# xen_teensy_motherboard_matrix_mki.net
KiCad netlist of a schematic drawn in EAGLE
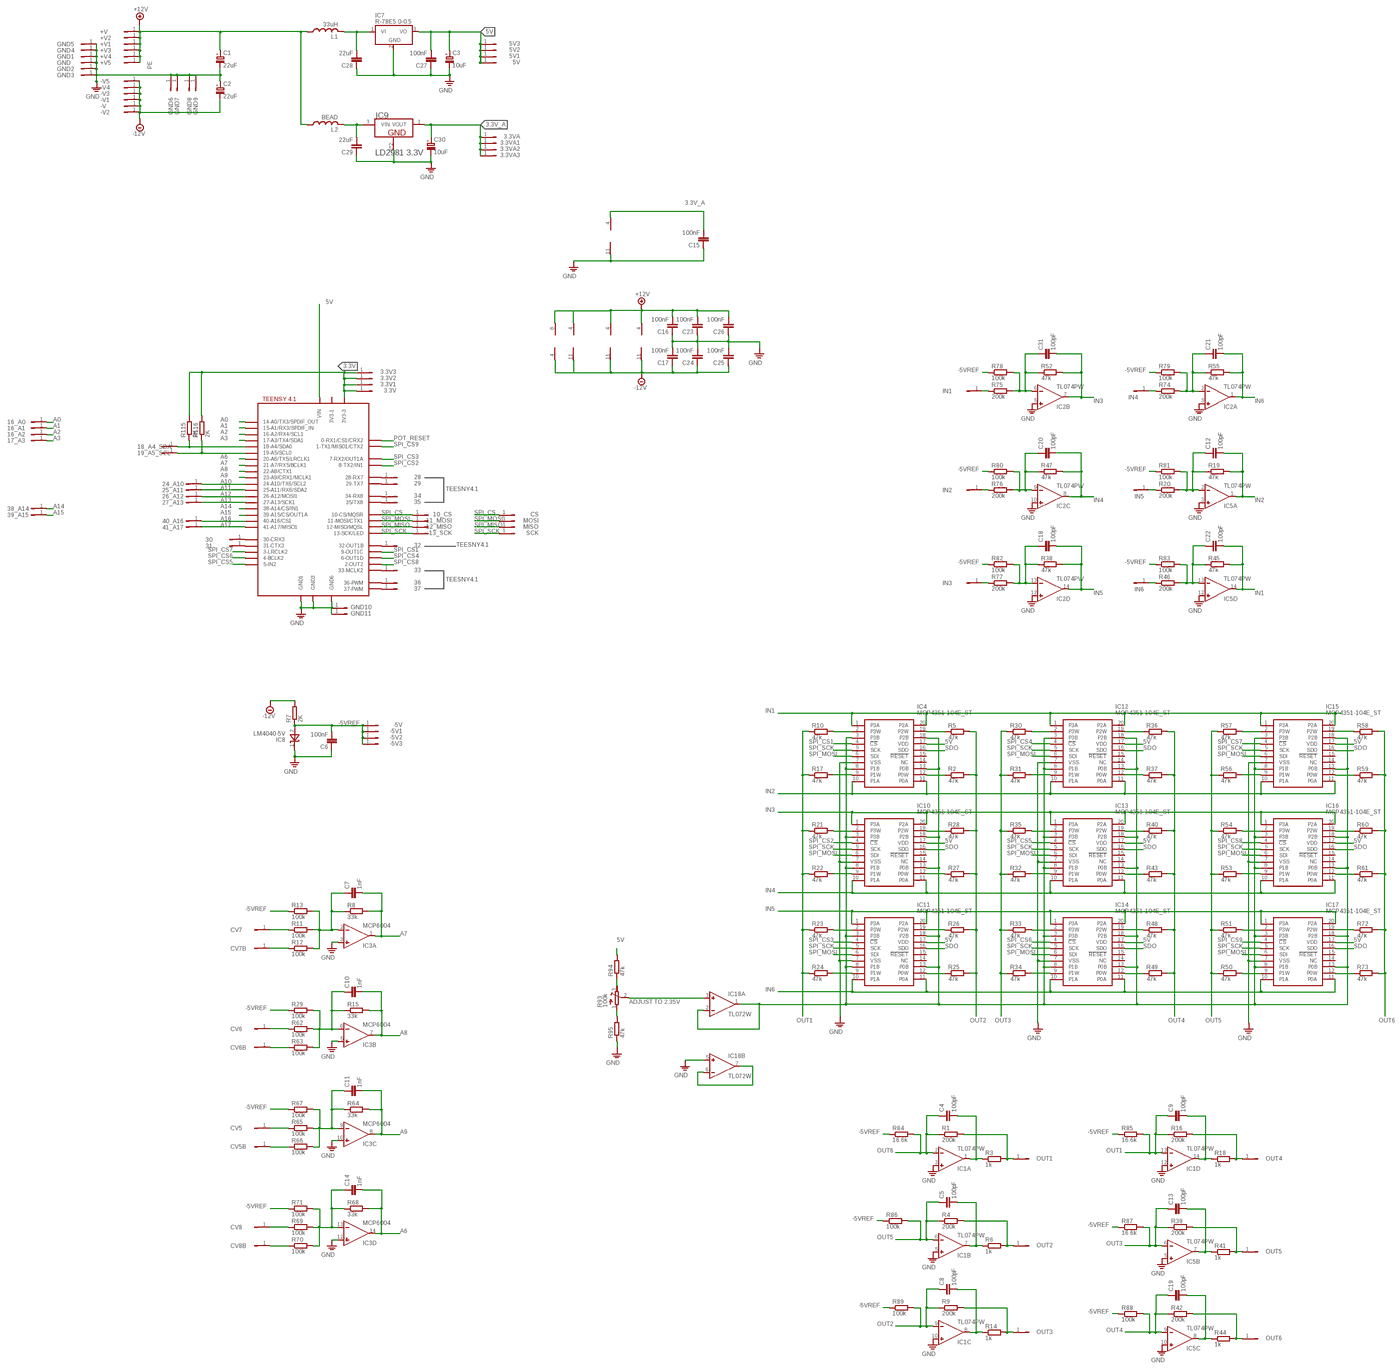
[diagram p0: schematic, sheet 1, overview]
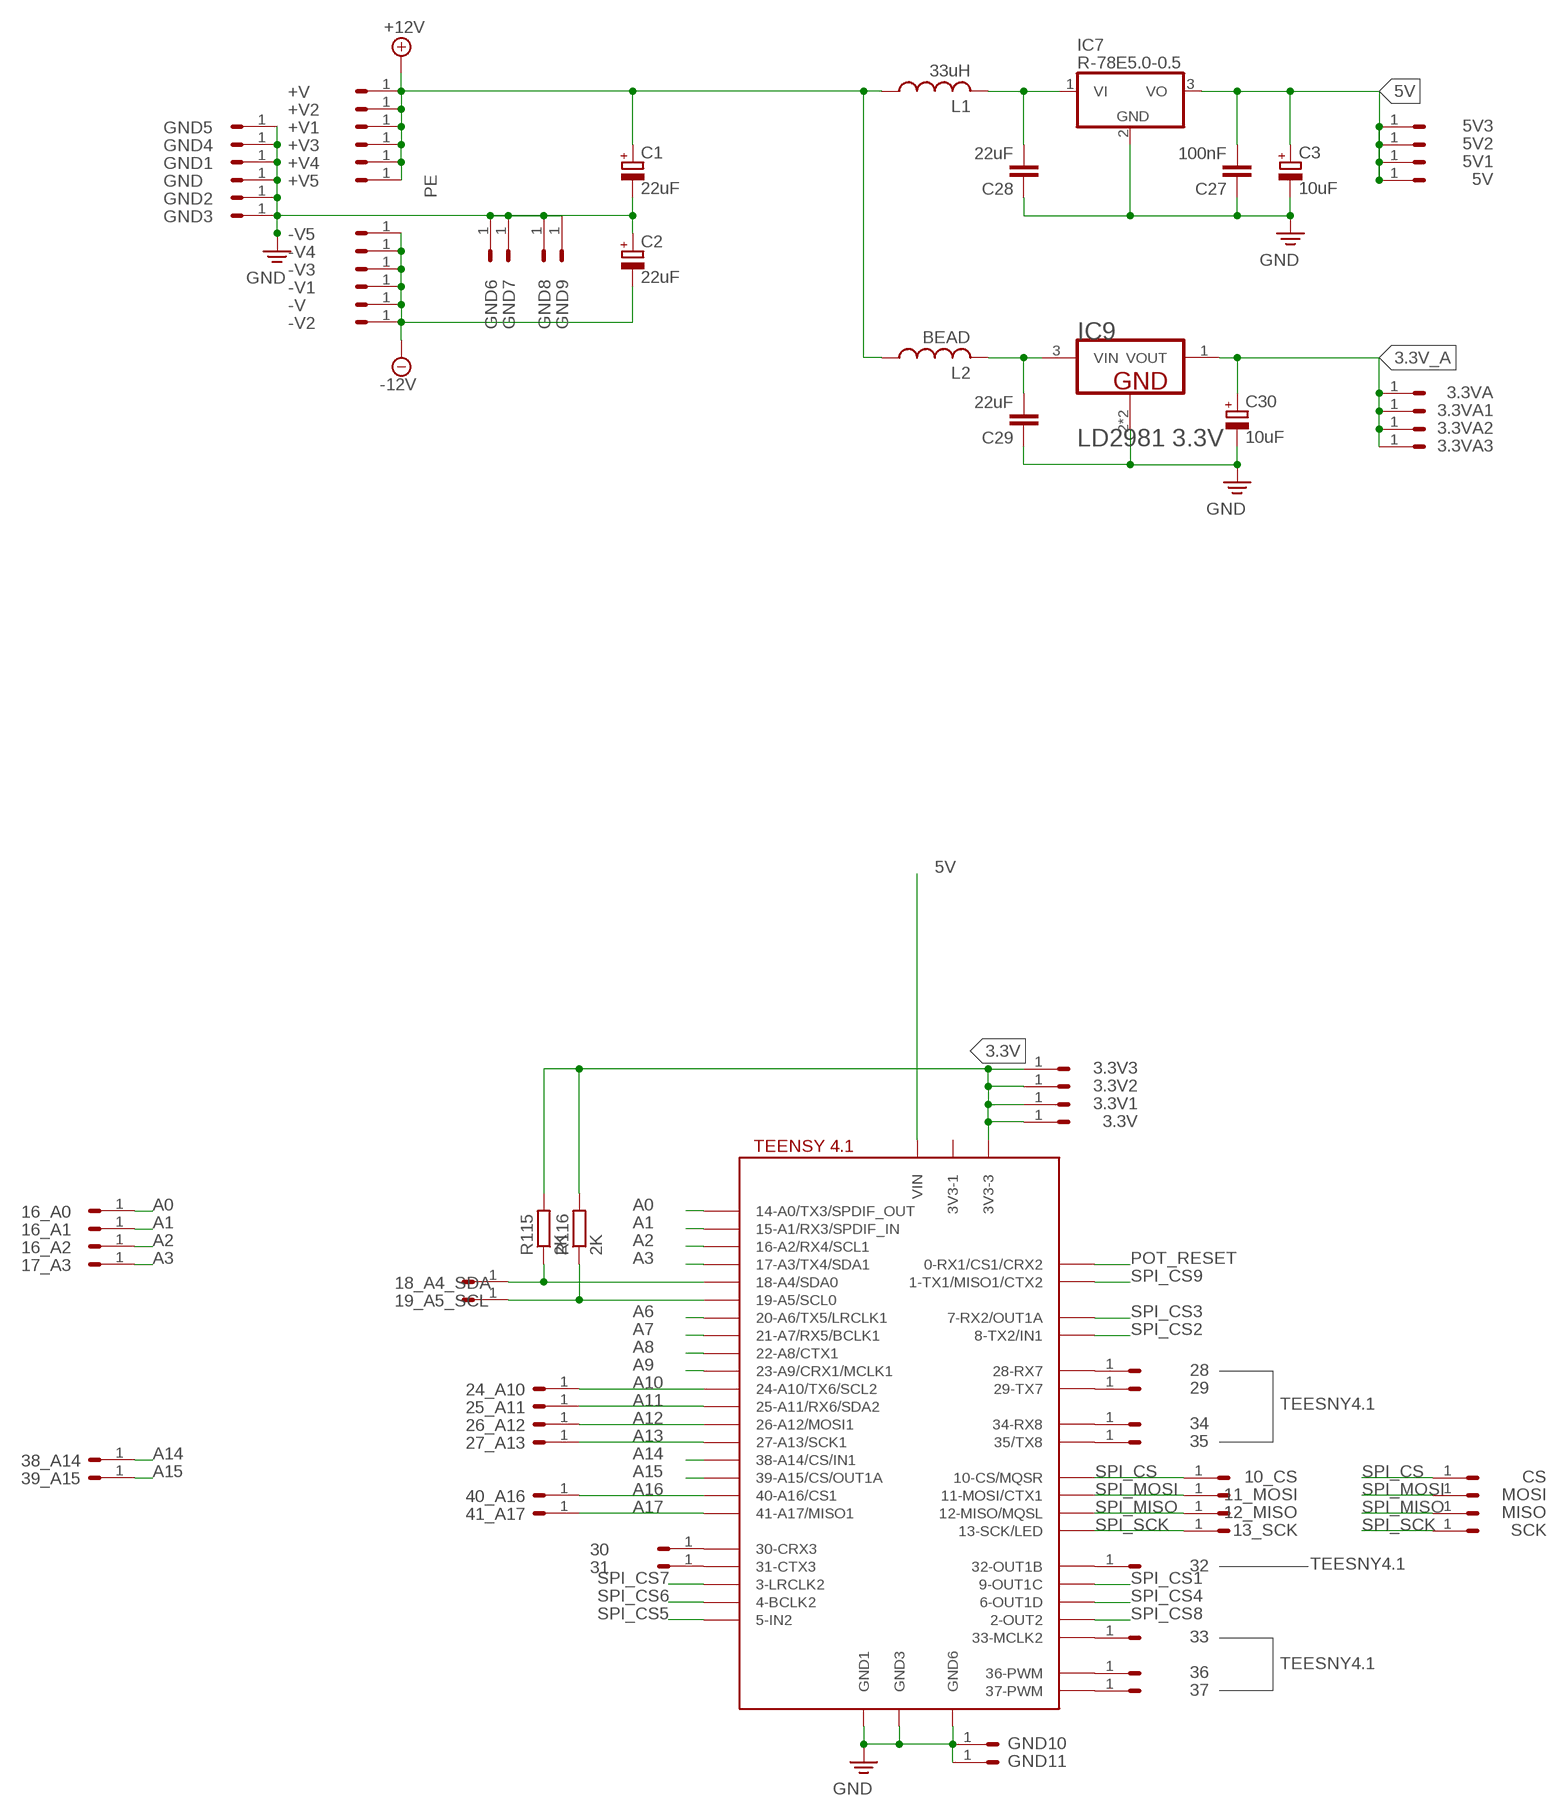
[diagram p1: schematic, sheet 1, part 1 of 4]
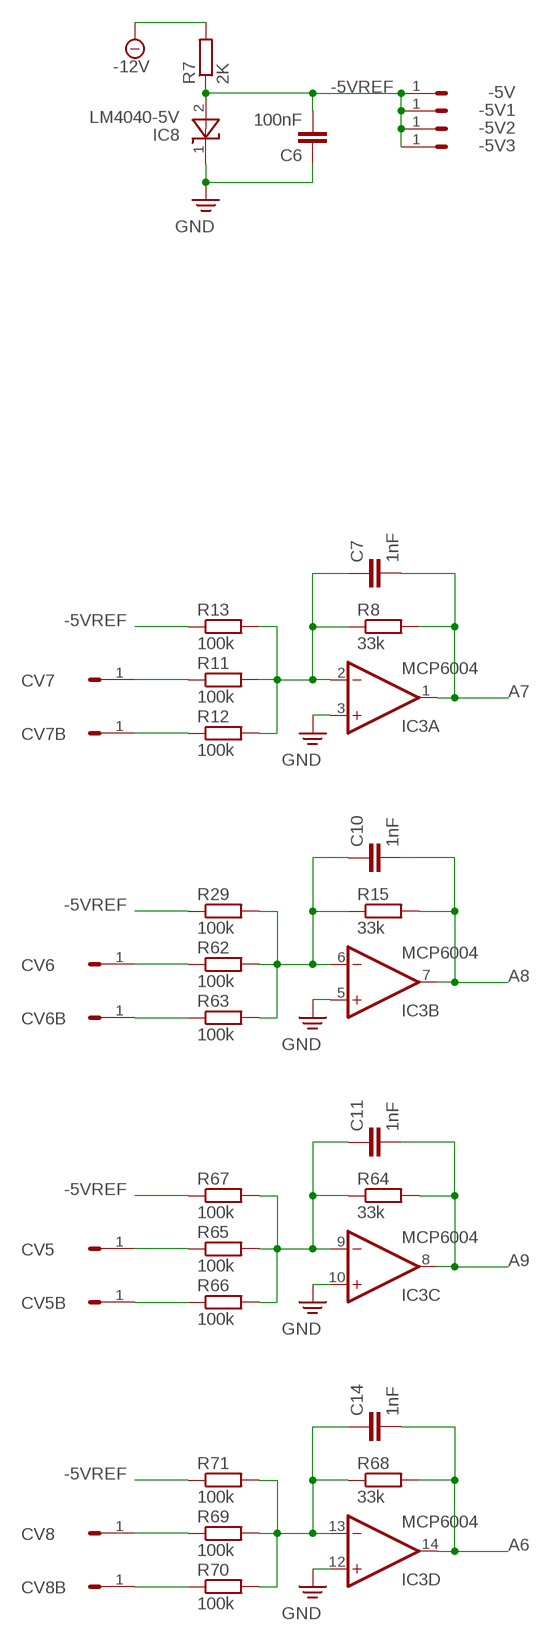
[diagram p2: schematic, sheet 1, part 2 of 4]
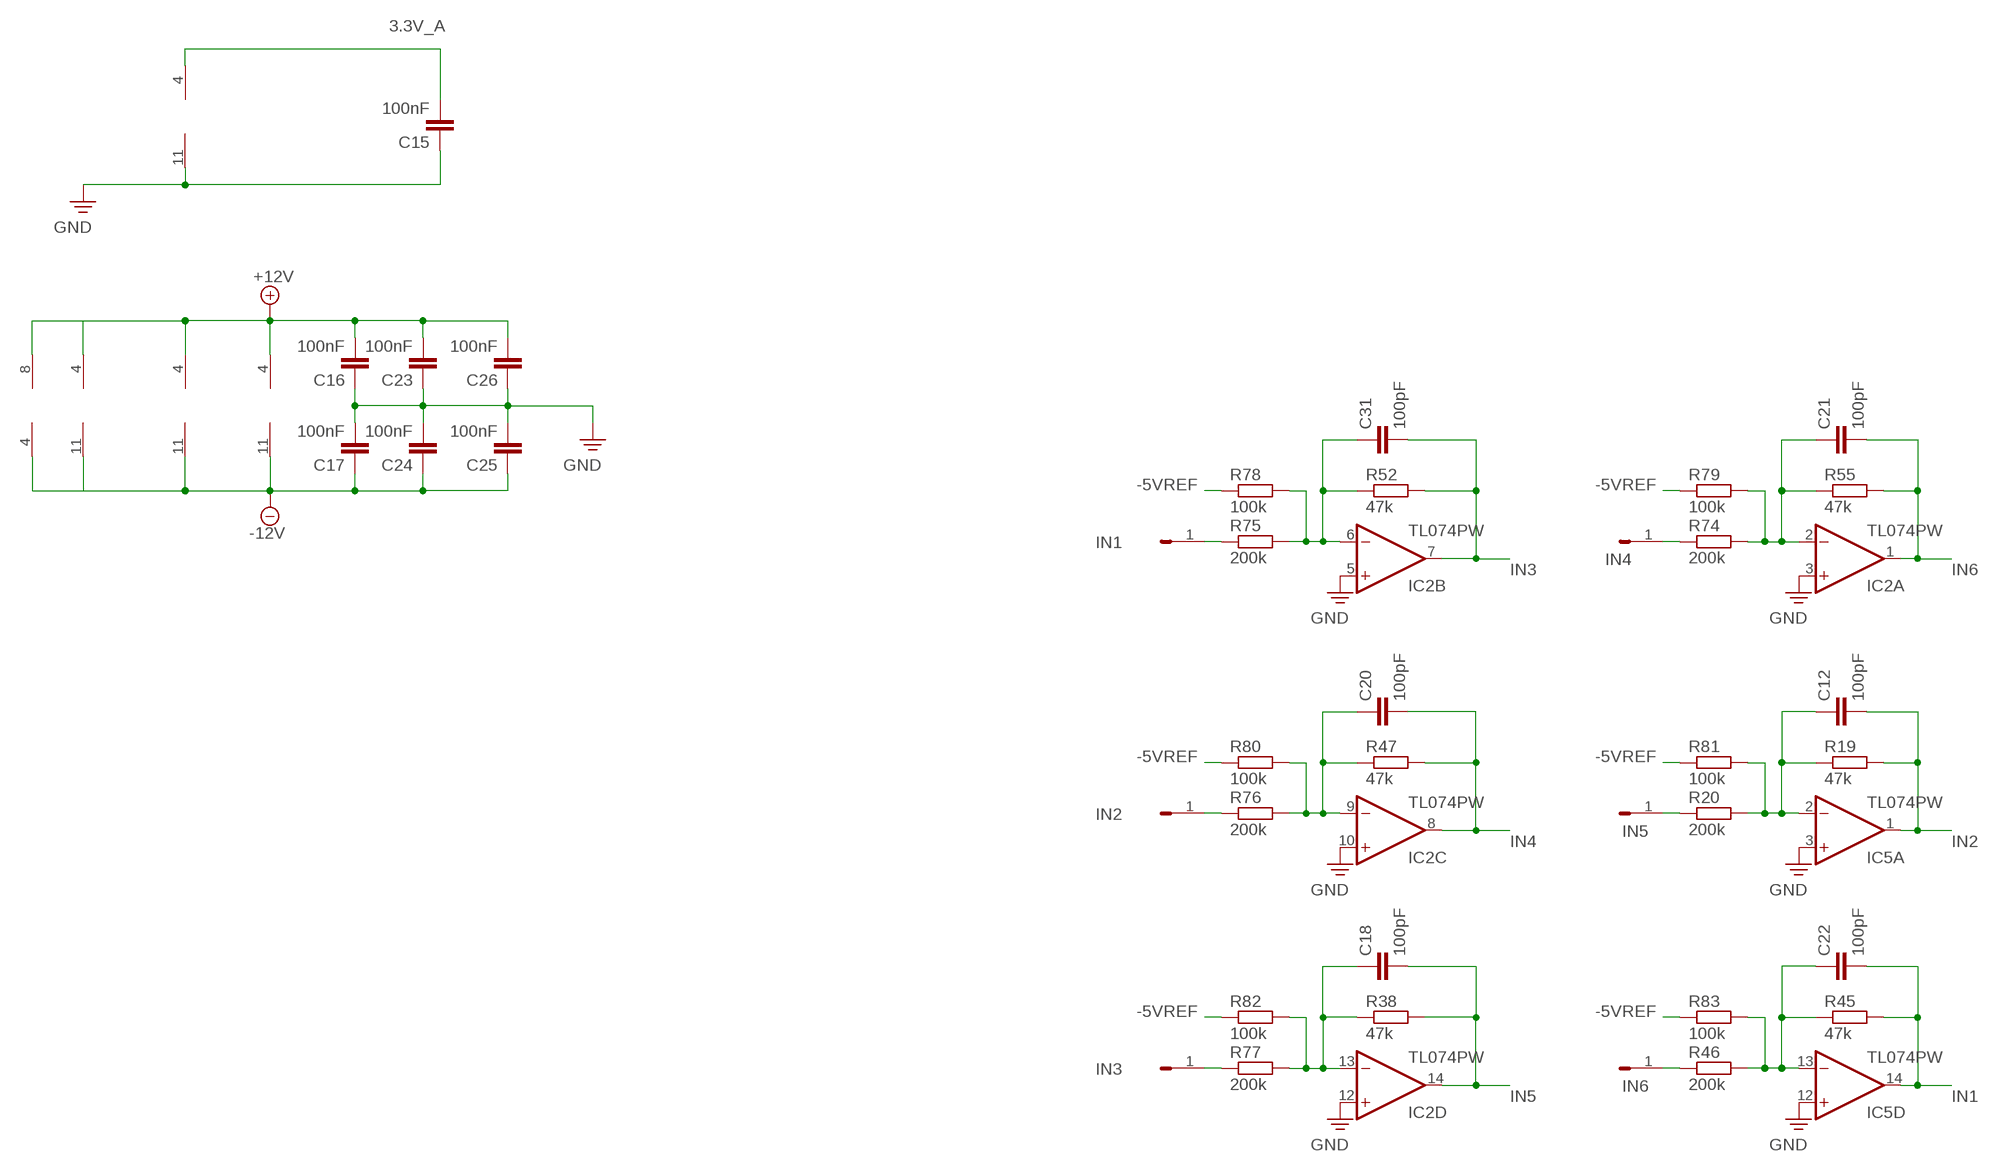
[diagram p3: schematic, sheet 1, part 3 of 4]
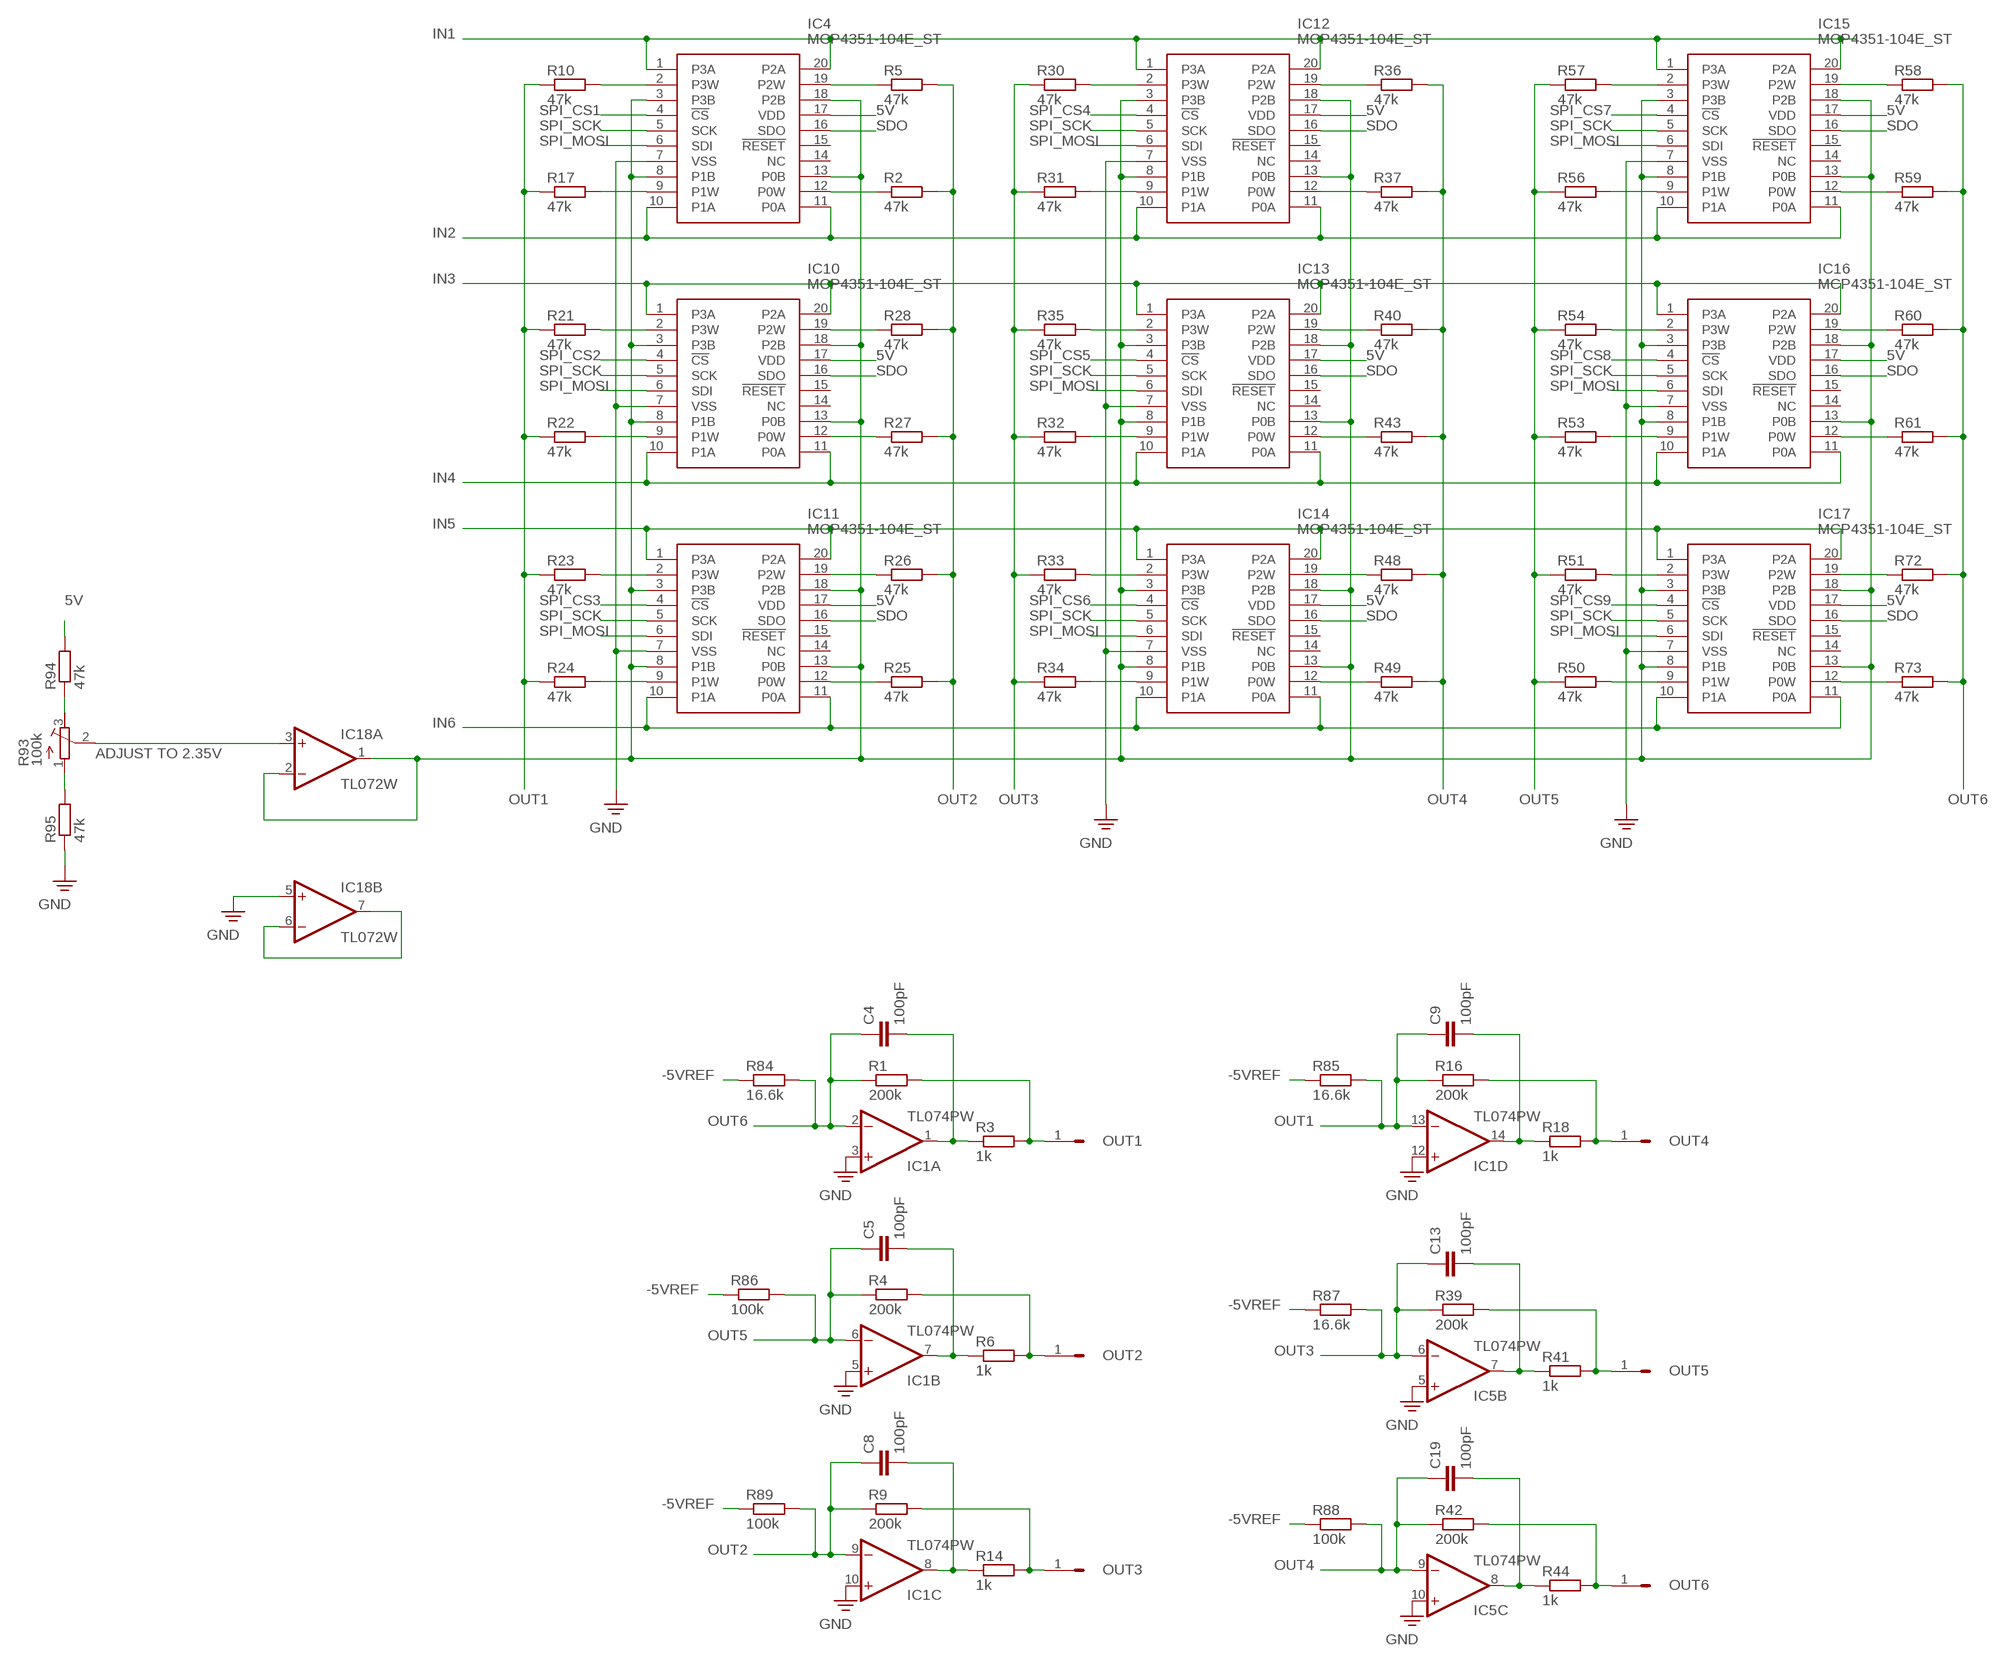
[diagram p4: schematic, sheet 1, part 4 of 4]

(export (version "E")
  (design (tool "Eeschema 10.0.6"))
  (components
    (comp (ref "+V")
      (value "HEADER/MALE/01")
      (footprint "eagle-import:HEADER_MALE_01")
      (fields (field (name "SPICEPREFIX") "X"))
      (libsource (lib "eagle-import") (part "HEADER/MALE/01"))
    )
    (comp (ref "+V1")
      (value "HEADER/MALE/01")
      (footprint "eagle-import:HEADER_MALE_01")
      (fields (field (name "SPICEPREFIX") "X"))
      (libsource (lib "eagle-import") (part "HEADER/MALE/01"))
    )
    (comp (ref "+V2")
      (value "HEADER/MALE/01")
      (footprint "eagle-import:HEADER_MALE_01")
      (fields (field (name "SPICEPREFIX") "X"))
      (libsource (lib "eagle-import") (part "HEADER/MALE/01"))
    )
    (comp (ref "+V3")
      (value "HEADER/MALE/01")
      (footprint "eagle-import:HEADER_MALE_01")
      (fields (field (name "SPICEPREFIX") "X"))
      (libsource (lib "eagle-import") (part "HEADER/MALE/01"))
    )
    (comp (ref "+V4")
      (value "HEADER/MALE/01")
      (footprint "eagle-import:HEADER_MALE_01")
      (fields (field (name "SPICEPREFIX") "X"))
      (libsource (lib "eagle-import") (part "HEADER/MALE/01"))
    )
    (comp (ref "+V5")
      (value "HEADER/MALE/01")
      (footprint "eagle-import:HEADER_MALE_01")
      (fields (field (name "SPICEPREFIX") "X"))
      (libsource (lib "eagle-import") (part "HEADER/MALE/01"))
    )
    (comp (ref "-5V")
      (value "HEADER/MALE/01")
      (footprint "eagle-import:HEADER_MALE_01")
      (fields (field (name "SPICEPREFIX") "X"))
      (libsource (lib "eagle-import") (part "HEADER/MALE/01"))
    )
    (comp (ref "-5V1")
      (value "HEADER/MALE/01")
      (footprint "eagle-import:HEADER_MALE_01")
      (fields (field (name "SPICEPREFIX") "X"))
      (libsource (lib "eagle-import") (part "HEADER/MALE/01"))
    )
    (comp (ref "-5V2")
      (value "HEADER/MALE/01")
      (footprint "eagle-import:HEADER_MALE_01")
      (fields (field (name "SPICEPREFIX") "X"))
      (libsource (lib "eagle-import") (part "HEADER/MALE/01"))
    )
    (comp (ref "-5V3")
      (value "HEADER/MALE/01")
      (footprint "eagle-import:HEADER_MALE_01")
      (fields (field (name "SPICEPREFIX") "X"))
      (libsource (lib "eagle-import") (part "HEADER/MALE/01"))
    )
    (comp (ref "-V")
      (value "HEADER/MALE/01")
      (footprint "eagle-import:HEADER_MALE_01")
      (fields (field (name "SPICEPREFIX") "X"))
      (libsource (lib "eagle-import") (part "HEADER/MALE/01"))
    )
    (comp (ref "-V1")
      (value "HEADER/MALE/01")
      (footprint "eagle-import:HEADER_MALE_01")
      (fields (field (name "SPICEPREFIX") "X"))
      (libsource (lib "eagle-import") (part "HEADER/MALE/01"))
    )
    (comp (ref "-V2")
      (value "HEADER/MALE/01")
      (footprint "eagle-import:HEADER_MALE_01")
      (fields (field (name "SPICEPREFIX") "X"))
      (libsource (lib "eagle-import") (part "HEADER/MALE/01"))
    )
    (comp (ref "-V3")
      (value "HEADER/MALE/01")
      (footprint "eagle-import:HEADER_MALE_01")
      (fields (field (name "SPICEPREFIX") "X"))
      (libsource (lib "eagle-import") (part "HEADER/MALE/01"))
    )
    (comp (ref "-V4")
      (value "HEADER/MALE/01")
      (footprint "eagle-import:HEADER_MALE_01")
      (fields (field (name "SPICEPREFIX") "X"))
      (libsource (lib "eagle-import") (part "HEADER/MALE/01"))
    )
    (comp (ref "-V5")
      (value "HEADER/MALE/01")
      (footprint "eagle-import:HEADER_MALE_01")
      (fields (field (name "SPICEPREFIX") "X"))
      (libsource (lib "eagle-import") (part "HEADER/MALE/01"))
    )
    (comp (ref "3.3V")
      (value "HEADER/MALE/01")
      (footprint "eagle-import:HEADER_MALE_01")
      (fields (field (name "SPICEPREFIX") "X"))
      (libsource (lib "eagle-import") (part "HEADER/MALE/01"))
    )
    (comp (ref "3.3V1")
      (value "HEADER/MALE/01")
      (footprint "eagle-import:HEADER_MALE_01")
      (fields (field (name "SPICEPREFIX") "X"))
      (libsource (lib "eagle-import") (part "HEADER/MALE/01"))
    )
    (comp (ref "3.3V2")
      (value "HEADER/MALE/01")
      (footprint "eagle-import:HEADER_MALE_01")
      (fields (field (name "SPICEPREFIX") "X"))
      (libsource (lib "eagle-import") (part "HEADER/MALE/01"))
    )
    (comp (ref "3.3V3")
      (value "HEADER/MALE/01")
      (footprint "eagle-import:HEADER_MALE_01")
      (fields (field (name "SPICEPREFIX") "X"))
      (libsource (lib "eagle-import") (part "HEADER/MALE/01"))
    )
    (comp (ref "3.3VA")
      (value "HEADER/MALE/01")
      (footprint "eagle-import:HEADER_MALE_01")
      (fields (field (name "SPICEPREFIX") "X"))
      (libsource (lib "eagle-import") (part "HEADER/MALE/01"))
    )
    (comp (ref "3.3VA1")
      (value "HEADER/MALE/01")
      (footprint "eagle-import:HEADER_MALE_01")
      (fields (field (name "SPICEPREFIX") "X"))
      (libsource (lib "eagle-import") (part "HEADER/MALE/01"))
    )
    (comp (ref "3.3VA2")
      (value "HEADER/MALE/01")
      (footprint "eagle-import:HEADER_MALE_01")
      (fields (field (name "SPICEPREFIX") "X"))
      (libsource (lib "eagle-import") (part "HEADER/MALE/01"))
    )
    (comp (ref "3.3VA3")
      (value "HEADER/MALE/01")
      (footprint "eagle-import:HEADER_MALE_01")
      (fields (field (name "SPICEPREFIX") "X"))
      (libsource (lib "eagle-import") (part "HEADER/MALE/01"))
    )
    (comp (ref "5V")
      (value "HEADER/MALE/01")
      (footprint "eagle-import:HEADER_MALE_01")
      (fields (field (name "SPICEPREFIX") "X"))
      (libsource (lib "eagle-import") (part "HEADER/MALE/01"))
    )
    (comp (ref "5V1")
      (value "HEADER/MALE/01")
      (footprint "eagle-import:HEADER_MALE_01")
      (fields (field (name "SPICEPREFIX") "X"))
      (libsource (lib "eagle-import") (part "HEADER/MALE/01"))
    )
    (comp (ref "5V2")
      (value "HEADER/MALE/01")
      (footprint "eagle-import:HEADER_MALE_01")
      (fields (field (name "SPICEPREFIX") "X"))
      (libsource (lib "eagle-import") (part "HEADER/MALE/01"))
    )
    (comp (ref "5V3")
      (value "HEADER/MALE/01")
      (footprint "eagle-import:HEADER_MALE_01")
      (fields (field (name "SPICEPREFIX") "X"))
      (libsource (lib "eagle-import") (part "HEADER/MALE/01"))
    )
    (comp (ref "10_CS")
      (value "HEADER/MALE/01")
      (footprint "eagle-import:HEADER_MALE_01")
      (fields (field (name "SPICEPREFIX") "X"))
      (libsource (lib "eagle-import") (part "HEADER/MALE/01"))
    )
    (comp (ref "11_MOSI")
      (value "HEADER/MALE/01")
      (footprint "eagle-import:HEADER_MALE_01")
      (fields (field (name "SPICEPREFIX") "X"))
      (libsource (lib "eagle-import") (part "HEADER/MALE/01"))
    )
    (comp (ref "12_MISO")
      (value "HEADER/MALE/01")
      (footprint "eagle-import:HEADER_MALE_01")
      (fields (field (name "SPICEPREFIX") "X"))
      (libsource (lib "eagle-import") (part "HEADER/MALE/01"))
    )
    (comp (ref "13_SCK")
      (value "HEADER/MALE/01")
      (footprint "eagle-import:HEADER_MALE_01")
      (fields (field (name "SPICEPREFIX") "X"))
      (libsource (lib "eagle-import") (part "HEADER/MALE/01"))
    )
    (comp (ref "16_A0")
      (value "HEADER/MALE/01")
      (footprint "eagle-import:HEADER_MALE_01")
      (fields (field (name "SPICEPREFIX") "X"))
      (libsource (lib "eagle-import") (part "HEADER/MALE/01"))
    )
    (comp (ref "16_A1")
      (value "HEADER/MALE/01")
      (footprint "eagle-import:HEADER_MALE_01")
      (fields (field (name "SPICEPREFIX") "X"))
      (libsource (lib "eagle-import") (part "HEADER/MALE/01"))
    )
    (comp (ref "16_A2")
      (value "HEADER/MALE/01")
      (footprint "eagle-import:HEADER_MALE_01")
      (fields (field (name "SPICEPREFIX") "X"))
      (libsource (lib "eagle-import") (part "HEADER/MALE/01"))
    )
    (comp (ref "17_A3")
      (value "HEADER/MALE/01")
      (footprint "eagle-import:HEADER_MALE_01")
      (fields (field (name "SPICEPREFIX") "X"))
      (libsource (lib "eagle-import") (part "HEADER/MALE/01"))
    )
    (comp (ref "18_A4_SDA")
      (value "HEADER/MALE/01")
      (footprint "eagle-import:HEADER_MALE_01")
      (fields (field (name "SPICEPREFIX") "X"))
      (libsource (lib "eagle-import") (part "HEADER/MALE/01"))
    )
    (comp (ref "19_A5_SCL")
      (value "HEADER/MALE/01")
      (footprint "eagle-import:HEADER_MALE_01")
      (fields (field (name "SPICEPREFIX") "X"))
      (libsource (lib "eagle-import") (part "HEADER/MALE/01"))
    )
    (comp (ref "24_A10")
      (value "HEADER/MALE/01")
      (footprint "eagle-import:HEADER_MALE_01")
      (fields (field (name "SPICEPREFIX") "X"))
      (libsource (lib "eagle-import") (part "HEADER/MALE/01"))
    )
    (comp (ref "25_A11")
      (value "HEADER/MALE/01")
      (footprint "eagle-import:HEADER_MALE_01")
      (fields (field (name "SPICEPREFIX") "X"))
      (libsource (lib "eagle-import") (part "HEADER/MALE/01"))
    )
    (comp (ref "26_A12")
      (value "HEADER/MALE/01")
      (footprint "eagle-import:HEADER_MALE_01")
      (fields (field (name "SPICEPREFIX") "X"))
      (libsource (lib "eagle-import") (part "HEADER/MALE/01"))
    )
    (comp (ref "27_A13")
      (value "HEADER/MALE/01")
      (footprint "eagle-import:HEADER_MALE_01")
      (fields (field (name "SPICEPREFIX") "X"))
      (libsource (lib "eagle-import") (part "HEADER/MALE/01"))
    )
    (comp (ref "28")
      (value "HEADER/MALE/01")
      (footprint "eagle-import:HEADER_MALE_01")
      (fields (field (name "SPICEPREFIX") "X"))
      (libsource (lib "eagle-import") (part "HEADER/MALE/01"))
    )
    (comp (ref "29")
      (value "HEADER/MALE/01")
      (footprint "eagle-import:HEADER_MALE_01")
      (fields (field (name "SPICEPREFIX") "X"))
      (libsource (lib "eagle-import") (part "HEADER/MALE/01"))
    )
    (comp (ref "30")
      (value "HEADER/MALE/01")
      (footprint "eagle-import:HEADER_MALE_01")
      (fields (field (name "SPICEPREFIX") "X"))
      (libsource (lib "eagle-import") (part "HEADER/MALE/01"))
    )
    (comp (ref "31")
      (value "HEADER/MALE/01")
      (footprint "eagle-import:HEADER_MALE_01")
      (fields (field (name "SPICEPREFIX") "X"))
      (libsource (lib "eagle-import") (part "HEADER/MALE/01"))
    )
    (comp (ref "32")
      (value "HEADER/MALE/01")
      (footprint "eagle-import:HEADER_MALE_01")
      (fields (field (name "SPICEPREFIX") "X"))
      (libsource (lib "eagle-import") (part "HEADER/MALE/01"))
    )
    (comp (ref "33")
      (value "HEADER/MALE/01")
      (footprint "eagle-import:HEADER_MALE_01")
      (fields (field (name "SPICEPREFIX") "X"))
      (libsource (lib "eagle-import") (part "HEADER/MALE/01"))
    )
    (comp (ref "34")
      (value "HEADER/MALE/01")
      (footprint "eagle-import:HEADER_MALE_01")
      (fields (field (name "SPICEPREFIX") "X"))
      (libsource (lib "eagle-import") (part "HEADER/MALE/01"))
    )
    (comp (ref "35")
      (value "HEADER/MALE/01")
      (footprint "eagle-import:HEADER_MALE_01")
      (fields (field (name "SPICEPREFIX") "X"))
      (libsource (lib "eagle-import") (part "HEADER/MALE/01"))
    )
    (comp (ref "36")
      (value "HEADER/MALE/01")
      (footprint "eagle-import:HEADER_MALE_01")
      (fields (field (name "SPICEPREFIX") "X"))
      (libsource (lib "eagle-import") (part "HEADER/MALE/01"))
    )
    (comp (ref "37")
      (value "HEADER/MALE/01")
      (footprint "eagle-import:HEADER_MALE_01")
      (fields (field (name "SPICEPREFIX") "X"))
      (libsource (lib "eagle-import") (part "HEADER/MALE/01"))
    )
    (comp (ref "38_A14")
      (value "HEADER/MALE/01")
      (footprint "eagle-import:HEADER_MALE_01")
      (fields (field (name "SPICEPREFIX") "X"))
      (libsource (lib "eagle-import") (part "HEADER/MALE/01"))
    )
    (comp (ref "39_A15")
      (value "HEADER/MALE/01")
      (footprint "eagle-import:HEADER_MALE_01")
      (fields (field (name "SPICEPREFIX") "X"))
      (libsource (lib "eagle-import") (part "HEADER/MALE/01"))
    )
    (comp (ref "40_A16")
      (value "HEADER/MALE/01")
      (footprint "eagle-import:HEADER_MALE_01")
      (fields (field (name "SPICEPREFIX") "X"))
      (libsource (lib "eagle-import") (part "HEADER/MALE/01"))
    )
    (comp (ref "41_A17")
      (value "HEADER/MALE/01")
      (footprint "eagle-import:HEADER_MALE_01")
      (fields (field (name "SPICEPREFIX") "X"))
      (libsource (lib "eagle-import") (part "HEADER/MALE/01"))
    )
    (comp (ref "C1")
      (value "22uF")
      (footprint "eagle-import:SV-C")
      (fields (field (name "SPICEPREFIX") "C"))
      (libsource (lib "eagle-import") (part "CAPACITOR/POLARIZEDSMDC"))
    )
    (comp (ref "C2")
      (value "22uF")
      (footprint "eagle-import:SV-C")
      (fields (field (name "SPICEPREFIX") "C"))
      (libsource (lib "eagle-import") (part "CAPACITOR/POLARIZEDSMDC"))
    )
    (comp (ref "C3")
      (value "10uF")
      (footprint "eagle-import:SV-B")
      (fields (field (name "SPICEPREFIX") "C"))
      (libsource (lib "eagle-import") (part "CAPACITOR/POLARIZEDSMDB"))
    )
    (comp (ref "C4")
      (value "100pF")
      (footprint "eagle-import:C0603")
      (libsource (lib "eagle-import") (part "CAPACITORC0603"))
    )
    (comp (ref "C5")
      (value "100pF")
      (footprint "eagle-import:C0603")
      (libsource (lib "eagle-import") (part "CAPACITORC0603"))
    )
    (comp (ref "C6")
      (value "100nF")
      (footprint "eagle-import:C0603")
      (libsource (lib "eagle-import") (part "CAPACITORC0603"))
    )
    (comp (ref "C7")
      (value "1nF")
      (footprint "eagle-import:C0603")
      (libsource (lib "eagle-import") (part "CAPACITORC0603"))
    )
    (comp (ref "C8")
      (value "100pF")
      (footprint "eagle-import:C0603")
      (libsource (lib "eagle-import") (part "CAPACITORC0603"))
    )
    (comp (ref "C9")
      (value "100pF")
      (footprint "eagle-import:C0603")
      (libsource (lib "eagle-import") (part "CAPACITORC0603"))
    )
    (comp (ref "C10")
      (value "1nF")
      (footprint "eagle-import:C0603")
      (libsource (lib "eagle-import") (part "CAPACITORC0603"))
    )
    (comp (ref "C11")
      (value "1nF")
      (footprint "eagle-import:C0603")
      (libsource (lib "eagle-import") (part "CAPACITORC0603"))
    )
    (comp (ref "C12")
      (value "100pF")
      (footprint "eagle-import:C0603")
      (libsource (lib "eagle-import") (part "CAPACITORC0603"))
    )
    (comp (ref "C13")
      (value "100pF")
      (footprint "eagle-import:C0603")
      (libsource (lib "eagle-import") (part "CAPACITORC0603"))
    )
    (comp (ref "C14")
      (value "1nF")
      (footprint "eagle-import:C0603")
      (libsource (lib "eagle-import") (part "CAPACITORC0603"))
    )
    (comp (ref "C15")
      (value "100nF")
      (footprint "eagle-import:C0603")
      (libsource (lib "eagle-import") (part "CAPACITORC0603"))
    )
    (comp (ref "C16")
      (value "100nF")
      (footprint "eagle-import:C0603")
      (libsource (lib "eagle-import") (part "CAPACITORC0603"))
    )
    (comp (ref "C17")
      (value "100nF")
      (footprint "eagle-import:C0603")
      (libsource (lib "eagle-import") (part "CAPACITORC0603"))
    )
    (comp (ref "C18")
      (value "100pF")
      (footprint "eagle-import:C0603")
      (libsource (lib "eagle-import") (part "CAPACITORC0603"))
    )
    (comp (ref "C19")
      (value "100pF")
      (footprint "eagle-import:C0603")
      (libsource (lib "eagle-import") (part "CAPACITORC0603"))
    )
    (comp (ref "C20")
      (value "100pF")
      (footprint "eagle-import:C0603")
      (libsource (lib "eagle-import") (part "CAPACITORC0603"))
    )
    (comp (ref "C21")
      (value "100pF")
      (footprint "eagle-import:C0603")
      (libsource (lib "eagle-import") (part "CAPACITORC0603"))
    )
    (comp (ref "C22")
      (value "100pF")
      (footprint "eagle-import:C0603")
      (libsource (lib "eagle-import") (part "CAPACITORC0603"))
    )
    (comp (ref "C23")
      (value "100nF")
      (footprint "eagle-import:C0603")
      (libsource (lib "eagle-import") (part "CAPACITORC0603"))
    )
    (comp (ref "C24")
      (value "100nF")
      (footprint "eagle-import:C0603")
      (libsource (lib "eagle-import") (part "CAPACITORC0603"))
    )
    (comp (ref "C25")
      (value "100nF")
      (footprint "eagle-import:C0603")
      (libsource (lib "eagle-import") (part "CAPACITORC0603"))
    )
    (comp (ref "C26")
      (value "100nF")
      (footprint "eagle-import:C0603")
      (libsource (lib "eagle-import") (part "CAPACITORC0603"))
    )
    (comp (ref "C27")
      (value "100nF")
      (footprint "eagle-import:C0603")
      (libsource (lib "eagle-import") (part "CAPACITORC0603"))
    )
    (comp (ref "C28")
      (value "22uF")
      (footprint "eagle-import:C0805")
      (libsource (lib "eagle-import") (part "CAPACITORC0805"))
    )
    (comp (ref "C29")
      (value "22uF")
      (footprint "eagle-import:C0805")
      (libsource (lib "eagle-import") (part "CAPACITORC0805"))
    )
    (comp (ref "C30")
      (value "10uF")
      (footprint "eagle-import:SV-B")
      (fields (field (name "SPICEPREFIX") "C"))
      (libsource (lib "eagle-import") (part "CAPACITOR/POLARIZEDSMDB"))
    )
    (comp (ref "C31")
      (value "100pF")
      (footprint "eagle-import:C0603")
      (libsource (lib "eagle-import") (part "CAPACITORC0603"))
    )
    (comp (ref "CS")
      (value "HEADER/MALE/01")
      (footprint "eagle-import:HEADER_MALE_01")
      (fields (field (name "SPICEPREFIX") "X"))
      (libsource (lib "eagle-import") (part "HEADER/MALE/01"))
    )
    (comp (ref "CV5")
      (value "HEADER/MALE/01")
      (footprint "eagle-import:HEADER_MALE_01")
      (fields (field (name "SPICEPREFIX") "X"))
      (libsource (lib "eagle-import") (part "HEADER/MALE/01"))
    )
    (comp (ref "CV5B")
      (value "HEADER/MALE/01")
      (footprint "eagle-import:HEADER_MALE_01")
      (fields (field (name "SPICEPREFIX") "X"))
      (libsource (lib "eagle-import") (part "HEADER/MALE/01"))
    )
    (comp (ref "CV6")
      (value "HEADER/MALE/01")
      (footprint "eagle-import:HEADER_MALE_01")
      (fields (field (name "SPICEPREFIX") "X"))
      (libsource (lib "eagle-import") (part "HEADER/MALE/01"))
    )
    (comp (ref "CV6B")
      (value "HEADER/MALE/01")
      (footprint "eagle-import:HEADER_MALE_01")
      (fields (field (name "SPICEPREFIX") "X"))
      (libsource (lib "eagle-import") (part "HEADER/MALE/01"))
    )
    (comp (ref "CV7")
      (value "HEADER/MALE/01")
      (footprint "eagle-import:HEADER_MALE_01")
      (fields (field (name "SPICEPREFIX") "X"))
      (libsource (lib "eagle-import") (part "HEADER/MALE/01"))
    )
    (comp (ref "CV7B")
      (value "HEADER/MALE/01")
      (footprint "eagle-import:HEADER_MALE_01")
      (fields (field (name "SPICEPREFIX") "X"))
      (libsource (lib "eagle-import") (part "HEADER/MALE/01"))
    )
    (comp (ref "CV8")
      (value "HEADER/MALE/01")
      (footprint "eagle-import:HEADER_MALE_01")
      (fields (field (name "SPICEPREFIX") "X"))
      (libsource (lib "eagle-import") (part "HEADER/MALE/01"))
    )
    (comp (ref "CV8B")
      (value "HEADER/MALE/01")
      (footprint "eagle-import:HEADER_MALE_01")
      (fields (field (name "SPICEPREFIX") "X"))
      (libsource (lib "eagle-import") (part "HEADER/MALE/01"))
    )
    (comp (ref "GND")
      (value "HEADER/MALE/01")
      (footprint "eagle-import:HEADER_MALE_01")
      (fields (field (name "SPICEPREFIX") "X"))
      (libsource (lib "eagle-import") (part "HEADER/MALE/01"))
    )
    (comp (ref "GND1")
      (value "HEADER/MALE/01")
      (footprint "eagle-import:HEADER_MALE_01")
      (fields (field (name "SPICEPREFIX") "X"))
      (libsource (lib "eagle-import") (part "HEADER/MALE/01"))
    )
    (comp (ref "GND2")
      (value "HEADER/MALE/01")
      (footprint "eagle-import:HEADER_MALE_01")
      (fields (field (name "SPICEPREFIX") "X"))
      (libsource (lib "eagle-import") (part "HEADER/MALE/01"))
    )
    (comp (ref "GND3")
      (value "HEADER/MALE/01")
      (footprint "eagle-import:HEADER_MALE_01")
      (fields (field (name "SPICEPREFIX") "X"))
      (libsource (lib "eagle-import") (part "HEADER/MALE/01"))
    )
    (comp (ref "GND4")
      (value "HEADER/MALE/01")
      (footprint "eagle-import:HEADER_MALE_01")
      (fields (field (name "SPICEPREFIX") "X"))
      (libsource (lib "eagle-import") (part "HEADER/MALE/01"))
    )
    (comp (ref "GND5")
      (value "HEADER/MALE/01")
      (footprint "eagle-import:HEADER_MALE_01")
      (fields (field (name "SPICEPREFIX") "X"))
      (libsource (lib "eagle-import") (part "HEADER/MALE/01"))
    )
    (comp (ref "GND6")
      (value "HEADER/MALE/01")
      (footprint "eagle-import:HEADER_MALE_01")
      (fields (field (name "SPICEPREFIX") "X"))
      (libsource (lib "eagle-import") (part "HEADER/MALE/01"))
    )
    (comp (ref "GND7")
      (value "HEADER/MALE/01")
      (footprint "eagle-import:HEADER_MALE_01")
      (fields (field (name "SPICEPREFIX") "X"))
      (libsource (lib "eagle-import") (part "HEADER/MALE/01"))
    )
    (comp (ref "GND8")
      (value "HEADER/MALE/01")
      (footprint "eagle-import:HEADER_MALE_01")
      (fields (field (name "SPICEPREFIX") "X"))
      (libsource (lib "eagle-import") (part "HEADER/MALE/01"))
    )
    (comp (ref "GND9")
      (value "HEADER/MALE/01")
      (footprint "eagle-import:HEADER_MALE_01")
      (fields (field (name "SPICEPREFIX") "X"))
      (libsource (lib "eagle-import") (part "HEADER/MALE/01"))
    )
    (comp (ref "GND10")
      (value "HEADER/MALE/01")
      (footprint "eagle-import:HEADER_MALE_01")
      (fields (field (name "SPICEPREFIX") "X"))
      (libsource (lib "eagle-import") (part "HEADER/MALE/01"))
    )
    (comp (ref "GND11")
      (value "HEADER/MALE/01")
      (footprint "eagle-import:HEADER_MALE_01")
      (fields (field (name "SPICEPREFIX") "X"))
      (libsource (lib "eagle-import") (part "HEADER/MALE/01"))
    )
    (comp (ref "IC1")
      (value "TL074PW")
      (footprint "eagle-import:TSSOP14")
      (libsource (lib "eagle-import") (part "TL074PW"))
    )
    (comp (ref "IC2")
      (value "TL074PW")
      (footprint "eagle-import:TSSOP14")
      (libsource (lib "eagle-import") (part "TL074PW"))
    )
    (comp (ref "IC3")
      (value "MCP6004")
      (footprint "eagle-import:TSSOP14")
      (libsource (lib "eagle-import") (part "TL074PW"))
    )
    (comp (ref "IC4")
      (value "MCP4351-104E_ST")
      (footprint "eagle-import:SOP65P640X120-20N")
      (fields
        (field (name "ARROW_PART_NUMBER") "MCP4351-104E/ST")
        (field (name "MOUSER_PART_NUMBER") "579-MCP4351104E/ST")
      )
      (libsource (lib "eagle-import") (part "MCP4351-104E_ST"))
    )
    (comp (ref "IC5")
      (value "TL074PW")
      (footprint "eagle-import:TSSOP14")
      (libsource (lib "eagle-import") (part "TL074PW"))
    )
    (comp (ref "IC6")
      (value "TEENSY41-OUTER")
      (footprint "eagle-import:TENNSY41-OUTER")
      (libsource (lib "eagle-import") (part "TEENSY41-OUTER"))
    )
    (comp (ref "IC7")
      (value "R-78E5.0-0.5")
      (footprint "eagle-import:WE78")
      (libsource (lib "eagle-import") (part "WE173950378"))
    )
    (comp (ref "IC8")
      (value "LM4040-5V")
      (footprint "eagle-import:SOT-23")
      (libsource (lib "eagle-import") (part "LM4040CYM3-2.5"))
    )
    (comp (ref "IC9")
      (value "LD2981 3.3V")
      (footprint "eagle-import:LD2981-SOT89")
      (fields (field (name "MF") "STMicroelectronics") (field (name "MPN") "LD2981CU33TR"))
      (libsource (lib "eagle-import") (part "LD2981LD2981-SOT89"))
    )
    (comp (ref "IC10")
      (value "MCP4351-104E_ST")
      (footprint "eagle-import:SOP65P640X120-20N")
      (fields
        (field (name "ARROW_PART_NUMBER") "MCP4351-104E/ST")
        (field (name "MOUSER_PART_NUMBER") "579-MCP4351104E/ST")
      )
      (libsource (lib "eagle-import") (part "MCP4351-104E_ST"))
    )
    (comp (ref "IC11")
      (value "MCP4351-104E_ST")
      (footprint "eagle-import:SOP65P640X120-20N")
      (fields
        (field (name "ARROW_PART_NUMBER") "MCP4351-104E/ST")
        (field (name "MOUSER_PART_NUMBER") "579-MCP4351104E/ST")
      )
      (libsource (lib "eagle-import") (part "MCP4351-104E_ST"))
    )
    (comp (ref "IC12")
      (value "MCP4351-104E_ST")
      (footprint "eagle-import:SOP65P640X120-20N")
      (fields
        (field (name "ARROW_PART_NUMBER") "MCP4351-104E/ST")
        (field (name "MOUSER_PART_NUMBER") "579-MCP4351104E/ST")
      )
      (libsource (lib "eagle-import") (part "MCP4351-104E_ST"))
    )
    (comp (ref "IC13")
      (value "MCP4351-104E_ST")
      (footprint "eagle-import:SOP65P640X120-20N")
      (fields
        (field (name "ARROW_PART_NUMBER") "MCP4351-104E/ST")
        (field (name "MOUSER_PART_NUMBER") "579-MCP4351104E/ST")
      )
      (libsource (lib "eagle-import") (part "MCP4351-104E_ST"))
    )
    (comp (ref "IC14")
      (value "MCP4351-104E_ST")
      (footprint "eagle-import:SOP65P640X120-20N")
      (fields
        (field (name "ARROW_PART_NUMBER") "MCP4351-104E/ST")
        (field (name "MOUSER_PART_NUMBER") "579-MCP4351104E/ST")
      )
      (libsource (lib "eagle-import") (part "MCP4351-104E_ST"))
    )
    (comp (ref "IC15")
      (value "MCP4351-104E_ST")
      (footprint "eagle-import:SOP65P640X120-20N")
      (fields
        (field (name "ARROW_PART_NUMBER") "MCP4351-104E/ST")
        (field (name "MOUSER_PART_NUMBER") "579-MCP4351104E/ST")
      )
      (libsource (lib "eagle-import") (part "MCP4351-104E_ST"))
    )
    (comp (ref "IC16")
      (value "MCP4351-104E_ST")
      (footprint "eagle-import:SOP65P640X120-20N")
      (fields
        (field (name "ARROW_PART_NUMBER") "MCP4351-104E/ST")
        (field (name "MOUSER_PART_NUMBER") "579-MCP4351104E/ST")
      )
      (libsource (lib "eagle-import") (part "MCP4351-104E_ST"))
    )
    (comp (ref "IC17")
      (value "MCP4351-104E_ST")
      (footprint "eagle-import:SOP65P640X120-20N")
      (fields
        (field (name "ARROW_PART_NUMBER") "MCP4351-104E/ST")
        (field (name "MOUSER_PART_NUMBER") "579-MCP4351104E/ST")
      )
      (libsource (lib "eagle-import") (part "MCP4351-104E_ST"))
    )
    (comp (ref "IC18")
      (value "TL072W")
      (footprint "eagle-import:TSSOP08")
      (libsource (lib "eagle-import") (part "TL072W"))
    )
    (comp (ref "IN1")
      (value "HEADER/MALE/01")
      (footprint "eagle-import:HEADER_MALE_01")
      (fields (field (name "SPICEPREFIX") "X"))
      (libsource (lib "eagle-import") (part "HEADER/MALE/01"))
    )
    (comp (ref "IN2")
      (value "HEADER/MALE/01")
      (footprint "eagle-import:HEADER_MALE_01")
      (fields (field (name "SPICEPREFIX") "X"))
      (libsource (lib "eagle-import") (part "HEADER/MALE/01"))
    )
    (comp (ref "IN3")
      (value "HEADER/MALE/01")
      (footprint "eagle-import:HEADER_MALE_01")
      (fields (field (name "SPICEPREFIX") "X"))
      (libsource (lib "eagle-import") (part "HEADER/MALE/01"))
    )
    (comp (ref "IN4")
      (value "HEADER/MALE/01")
      (footprint "eagle-import:HEADER_MALE_01")
      (fields (field (name "SPICEPREFIX") "X"))
      (libsource (lib "eagle-import") (part "HEADER/MALE/01"))
    )
    (comp (ref "IN5")
      (value "HEADER/MALE/01")
      (footprint "eagle-import:HEADER_MALE_01")
      (fields (field (name "SPICEPREFIX") "X"))
      (libsource (lib "eagle-import") (part "HEADER/MALE/01"))
    )
    (comp (ref "IN6")
      (value "HEADER/MALE/01")
      (footprint "eagle-import:HEADER_MALE_01")
      (fields (field (name "SPICEPREFIX") "X"))
      (libsource (lib "eagle-import") (part "HEADER/MALE/01"))
    )
    (comp (ref "L1")
      (value "33uH")
      (footprint "eagle-import:L2012C")
      (libsource (lib "eagle-import") (part "INDUCTORL2012C"))
    )
    (comp (ref "L2")
      (value "BEAD")
      (footprint "eagle-import:R0603")
      (libsource (lib "eagle-import") (part "INDUCTORL0603"))
    )
    (comp (ref "MISO")
      (value "HEADER/MALE/01")
      (footprint "eagle-import:HEADER_MALE_01")
      (fields (field (name "SPICEPREFIX") "X"))
      (libsource (lib "eagle-import") (part "HEADER/MALE/01"))
    )
    (comp (ref "MOSI")
      (value "HEADER/MALE/01")
      (footprint "eagle-import:HEADER_MALE_01")
      (fields (field (name "SPICEPREFIX") "X"))
      (libsource (lib "eagle-import") (part "HEADER/MALE/01"))
    )
    (comp (ref "OUT1")
      (value "HEADER/MALE/01")
      (footprint "eagle-import:HEADER_MALE_01")
      (fields (field (name "SPICEPREFIX") "X"))
      (libsource (lib "eagle-import") (part "HEADER/MALE/01"))
    )
    (comp (ref "OUT2")
      (value "HEADER/MALE/01")
      (footprint "eagle-import:HEADER_MALE_01")
      (fields (field (name "SPICEPREFIX") "X"))
      (libsource (lib "eagle-import") (part "HEADER/MALE/01"))
    )
    (comp (ref "OUT3")
      (value "HEADER/MALE/01")
      (footprint "eagle-import:HEADER_MALE_01")
      (fields (field (name "SPICEPREFIX") "X"))
      (libsource (lib "eagle-import") (part "HEADER/MALE/01"))
    )
    (comp (ref "OUT4")
      (value "HEADER/MALE/01")
      (footprint "eagle-import:HEADER_MALE_01")
      (fields (field (name "SPICEPREFIX") "X"))
      (libsource (lib "eagle-import") (part "HEADER/MALE/01"))
    )
    (comp (ref "OUT5")
      (value "HEADER/MALE/01")
      (footprint "eagle-import:HEADER_MALE_01")
      (fields (field (name "SPICEPREFIX") "X"))
      (libsource (lib "eagle-import") (part "HEADER/MALE/01"))
    )
    (comp (ref "OUT6")
      (value "HEADER/MALE/01")
      (footprint "eagle-import:HEADER_MALE_01")
      (fields (field (name "SPICEPREFIX") "X"))
      (libsource (lib "eagle-import") (part "HEADER/MALE/01"))
    )
    (comp (ref "R1")
      (value "200k")
      (footprint "eagle-import:R0603")
      (libsource (lib "eagle-import") (part "RESISTOR"))
    )
    (comp (ref "R2")
      (value "47k")
      (footprint "eagle-import:R0603")
      (libsource (lib "eagle-import") (part "RESISTOR"))
    )
    (comp (ref "R3")
      (value "1k")
      (footprint "eagle-import:R0603")
      (libsource (lib "eagle-import") (part "RESISTOR"))
    )
    (comp (ref "R4")
      (value "200k")
      (footprint "eagle-import:R0603")
      (libsource (lib "eagle-import") (part "RESISTOR"))
    )
    (comp (ref "R5")
      (value "47k")
      (footprint "eagle-import:R0603")
      (libsource (lib "eagle-import") (part "RESISTOR"))
    )
    (comp (ref "R6")
      (value "1k")
      (footprint "eagle-import:R0603")
      (libsource (lib "eagle-import") (part "RESISTOR"))
    )
    (comp (ref "R7")
      (value "2K")
      (footprint "eagle-import:R0603")
      (libsource (lib "eagle-import") (part "RESISTOR"))
    )
    (comp (ref "R8")
      (value "33k")
      (footprint "eagle-import:R0603")
      (libsource (lib "eagle-import") (part "RESISTOR"))
    )
    (comp (ref "R9")
      (value "200k")
      (footprint "eagle-import:R0603")
      (libsource (lib "eagle-import") (part "RESISTOR"))
    )
    (comp (ref "R10")
      (value "47k")
      (footprint "eagle-import:R0603")
      (libsource (lib "eagle-import") (part "RESISTOR"))
    )
    (comp (ref "R11")
      (value "100k")
      (footprint "eagle-import:R0603")
      (libsource (lib "eagle-import") (part "RESISTOR"))
    )
    (comp (ref "R12")
      (value "100k")
      (footprint "eagle-import:R0603")
      (libsource (lib "eagle-import") (part "RESISTOR"))
    )
    (comp (ref "R13")
      (value "100k")
      (footprint "eagle-import:R0603")
      (libsource (lib "eagle-import") (part "RESISTOR"))
    )
    (comp (ref "R14")
      (value "1k")
      (footprint "eagle-import:R0603")
      (libsource (lib "eagle-import") (part "RESISTOR"))
    )
    (comp (ref "R15")
      (value "33k")
      (footprint "eagle-import:R0603")
      (libsource (lib "eagle-import") (part "RESISTOR"))
    )
    (comp (ref "R16")
      (value "200k")
      (footprint "eagle-import:R0603")
      (libsource (lib "eagle-import") (part "RESISTOR"))
    )
    (comp (ref "R17")
      (value "47k")
      (footprint "eagle-import:R0603")
      (libsource (lib "eagle-import") (part "RESISTOR"))
    )
    (comp (ref "R18")
      (value "1k")
      (footprint "eagle-import:R0603")
      (libsource (lib "eagle-import") (part "RESISTOR"))
    )
    (comp (ref "R19")
      (value "47k")
      (footprint "eagle-import:R0603")
      (libsource (lib "eagle-import") (part "RESISTOR"))
    )
    (comp (ref "R20")
      (value "200k")
      (footprint "eagle-import:R0603")
      (libsource (lib "eagle-import") (part "RESISTOR"))
    )
    (comp (ref "R21")
      (value "47k")
      (footprint "eagle-import:R0603")
      (libsource (lib "eagle-import") (part "RESISTOR"))
    )
    (comp (ref "R22")
      (value "47k")
      (footprint "eagle-import:R0603")
      (libsource (lib "eagle-import") (part "RESISTOR"))
    )
    (comp (ref "R23")
      (value "47k")
      (footprint "eagle-import:R0603")
      (libsource (lib "eagle-import") (part "RESISTOR"))
    )
    (comp (ref "R24")
      (value "47k")
      (footprint "eagle-import:R0603")
      (libsource (lib "eagle-import") (part "RESISTOR"))
    )
    (comp (ref "R25")
      (value "47k")
      (footprint "eagle-import:R0603")
      (libsource (lib "eagle-import") (part "RESISTOR"))
    )
    (comp (ref "R26")
      (value "47k")
      (footprint "eagle-import:R0603")
      (libsource (lib "eagle-import") (part "RESISTOR"))
    )
    (comp (ref "R27")
      (value "47k")
      (footprint "eagle-import:R0603")
      (libsource (lib "eagle-import") (part "RESISTOR"))
    )
    (comp (ref "R28")
      (value "47k")
      (footprint "eagle-import:R0603")
      (libsource (lib "eagle-import") (part "RESISTOR"))
    )
    (comp (ref "R29")
      (value "100k")
      (footprint "eagle-import:R0603")
      (libsource (lib "eagle-import") (part "RESISTOR"))
    )
    (comp (ref "R30")
      (value "47k")
      (footprint "eagle-import:R0603")
      (libsource (lib "eagle-import") (part "RESISTOR"))
    )
    (comp (ref "R31")
      (value "47k")
      (footprint "eagle-import:R0603")
      (libsource (lib "eagle-import") (part "RESISTOR"))
    )
    (comp (ref "R32")
      (value "47k")
      (footprint "eagle-import:R0603")
      (libsource (lib "eagle-import") (part "RESISTOR"))
    )
    (comp (ref "R33")
      (value "47k")
      (footprint "eagle-import:R0603")
      (libsource (lib "eagle-import") (part "RESISTOR"))
    )
    (comp (ref "R34")
      (value "47k")
      (footprint "eagle-import:R0603")
      (libsource (lib "eagle-import") (part "RESISTOR"))
    )
    (comp (ref "R35")
      (value "47k")
      (footprint "eagle-import:R0603")
      (libsource (lib "eagle-import") (part "RESISTOR"))
    )
    (comp (ref "R36")
      (value "47k")
      (footprint "eagle-import:R0603")
      (libsource (lib "eagle-import") (part "RESISTOR"))
    )
    (comp (ref "R37")
      (value "47k")
      (footprint "eagle-import:R0603")
      (libsource (lib "eagle-import") (part "RESISTOR"))
    )
    (comp (ref "R38")
      (value "47k")
      (footprint "eagle-import:R0603")
      (libsource (lib "eagle-import") (part "RESISTOR"))
    )
    (comp (ref "R39")
      (value "200k")
      (footprint "eagle-import:R0603")
      (libsource (lib "eagle-import") (part "RESISTOR"))
    )
    (comp (ref "R40")
      (value "47k")
      (footprint "eagle-import:R0603")
      (libsource (lib "eagle-import") (part "RESISTOR"))
    )
    (comp (ref "R41")
      (value "1k")
      (footprint "eagle-import:R0603")
      (libsource (lib "eagle-import") (part "RESISTOR"))
    )
    (comp (ref "R42")
      (value "200k")
      (footprint "eagle-import:R0603")
      (libsource (lib "eagle-import") (part "RESISTOR"))
    )
    (comp (ref "R43")
      (value "47k")
      (footprint "eagle-import:R0603")
      (libsource (lib "eagle-import") (part "RESISTOR"))
    )
    (comp (ref "R44")
      (value "1k")
      (footprint "eagle-import:R0603")
      (libsource (lib "eagle-import") (part "RESISTOR"))
    )
    (comp (ref "R45")
      (value "47k")
      (footprint "eagle-import:R0603")
      (libsource (lib "eagle-import") (part "RESISTOR"))
    )
    (comp (ref "R46")
      (value "200k")
      (footprint "eagle-import:R0603")
      (libsource (lib "eagle-import") (part "RESISTOR"))
    )
    (comp (ref "R47")
      (value "47k")
      (footprint "eagle-import:R0603")
      (libsource (lib "eagle-import") (part "RESISTOR"))
    )
    (comp (ref "R48")
      (value "47k")
      (footprint "eagle-import:R0603")
      (libsource (lib "eagle-import") (part "RESISTOR"))
    )
    (comp (ref "R49")
      (value "47k")
      (footprint "eagle-import:R0603")
      (libsource (lib "eagle-import") (part "RESISTOR"))
    )
    (comp (ref "R50")
      (value "47k")
      (footprint "eagle-import:R0603")
      (libsource (lib "eagle-import") (part "RESISTOR"))
    )
    (comp (ref "R51")
      (value "47k")
      (footprint "eagle-import:R0603")
      (libsource (lib "eagle-import") (part "RESISTOR"))
    )
    (comp (ref "R52")
      (value "47k")
      (footprint "eagle-import:R0603")
      (libsource (lib "eagle-import") (part "RESISTOR"))
    )
    (comp (ref "R53")
      (value "47k")
      (footprint "eagle-import:R0603")
      (libsource (lib "eagle-import") (part "RESISTOR"))
    )
    (comp (ref "R54")
      (value "47k")
      (footprint "eagle-import:R0603")
      (libsource (lib "eagle-import") (part "RESISTOR"))
    )
    (comp (ref "R55")
      (value "47k")
      (footprint "eagle-import:R0603")
      (libsource (lib "eagle-import") (part "RESISTOR"))
    )
    (comp (ref "R56")
      (value "47k")
      (footprint "eagle-import:R0603")
      (libsource (lib "eagle-import") (part "RESISTOR"))
    )
    (comp (ref "R57")
      (value "47k")
      (footprint "eagle-import:R0603")
      (libsource (lib "eagle-import") (part "RESISTOR"))
    )
    (comp (ref "R58")
      (value "47k")
      (footprint "eagle-import:R0603")
      (libsource (lib "eagle-import") (part "RESISTOR"))
    )
    (comp (ref "R59")
      (value "47k")
      (footprint "eagle-import:R0603")
      (libsource (lib "eagle-import") (part "RESISTOR"))
    )
    (comp (ref "R60")
      (value "47k")
      (footprint "eagle-import:R0603")
      (libsource (lib "eagle-import") (part "RESISTOR"))
    )
    (comp (ref "R61")
      (value "47k")
      (footprint "eagle-import:R0603")
      (libsource (lib "eagle-import") (part "RESISTOR"))
    )
    (comp (ref "R62")
      (value "100k")
      (footprint "eagle-import:R0603")
      (libsource (lib "eagle-import") (part "RESISTOR"))
    )
    (comp (ref "R63")
      (value "100k")
      (footprint "eagle-import:R0603")
      (libsource (lib "eagle-import") (part "RESISTOR"))
    )
    (comp (ref "R64")
      (value "33k")
      (footprint "eagle-import:R0603")
      (libsource (lib "eagle-import") (part "RESISTOR"))
    )
    (comp (ref "R65")
      (value "100k")
      (footprint "eagle-import:R0603")
      (libsource (lib "eagle-import") (part "RESISTOR"))
    )
    (comp (ref "R66")
      (value "100k")
      (footprint "eagle-import:R0603")
      (libsource (lib "eagle-import") (part "RESISTOR"))
    )
    (comp (ref "R67")
      (value "100k")
      (footprint "eagle-import:R0603")
      (libsource (lib "eagle-import") (part "RESISTOR"))
    )
    (comp (ref "R68")
      (value "33k")
      (footprint "eagle-import:R0603")
      (libsource (lib "eagle-import") (part "RESISTOR"))
    )
    (comp (ref "R69")
      (value "100k")
      (footprint "eagle-import:R0603")
      (libsource (lib "eagle-import") (part "RESISTOR"))
    )
    (comp (ref "R70")
      (value "100k")
      (footprint "eagle-import:R0603")
      (libsource (lib "eagle-import") (part "RESISTOR"))
    )
    (comp (ref "R71")
      (value "100k")
      (footprint "eagle-import:R0603")
      (libsource (lib "eagle-import") (part "RESISTOR"))
    )
    (comp (ref "R72")
      (value "47k")
      (footprint "eagle-import:R0603")
      (libsource (lib "eagle-import") (part "RESISTOR"))
    )
    (comp (ref "R73")
      (value "47k")
      (footprint "eagle-import:R0603")
      (libsource (lib "eagle-import") (part "RESISTOR"))
    )
    (comp (ref "R74")
      (value "200k")
      (footprint "eagle-import:R0603")
      (libsource (lib "eagle-import") (part "RESISTOR"))
    )
    (comp (ref "R75")
      (value "200k")
      (footprint "eagle-import:R0603")
      (libsource (lib "eagle-import") (part "RESISTOR"))
    )
    (comp (ref "R76")
      (value "200k")
      (footprint "eagle-import:R0603")
      (libsource (lib "eagle-import") (part "RESISTOR"))
    )
    (comp (ref "R77")
      (value "200k")
      (footprint "eagle-import:R0603")
      (libsource (lib "eagle-import") (part "RESISTOR"))
    )
    (comp (ref "R78")
      (value "100k")
      (footprint "eagle-import:R0603")
      (libsource (lib "eagle-import") (part "RESISTOR"))
    )
    (comp (ref "R79")
      (value "100k")
      (footprint "eagle-import:R0603")
      (libsource (lib "eagle-import") (part "RESISTOR"))
    )
    (comp (ref "R80")
      (value "100k")
      (footprint "eagle-import:R0603")
      (libsource (lib "eagle-import") (part "RESISTOR"))
    )
    (comp (ref "R81")
      (value "100k")
      (footprint "eagle-import:R0603")
      (libsource (lib "eagle-import") (part "RESISTOR"))
    )
    (comp (ref "R82")
      (value "100k")
      (footprint "eagle-import:R0603")
      (libsource (lib "eagle-import") (part "RESISTOR"))
    )
    (comp (ref "R83")
      (value "100k")
      (footprint "eagle-import:R0603")
      (libsource (lib "eagle-import") (part "RESISTOR"))
    )
    (comp (ref "R84")
      (value "16.6k")
      (footprint "eagle-import:R0603")
      (libsource (lib "eagle-import") (part "RESISTOR"))
    )
    (comp (ref "R85")
      (value "16.6k")
      (footprint "eagle-import:R0603")
      (libsource (lib "eagle-import") (part "RESISTOR"))
    )
    (comp (ref "R86")
      (value "100k")
      (footprint "eagle-import:R0603")
      (libsource (lib "eagle-import") (part "RESISTOR"))
    )
    (comp (ref "R87")
      (value "16.6k")
      (footprint "eagle-import:R0603")
      (libsource (lib "eagle-import") (part "RESISTOR"))
    )
    (comp (ref "R88")
      (value "100k")
      (footprint "eagle-import:R0603")
      (libsource (lib "eagle-import") (part "RESISTOR"))
    )
    (comp (ref "R89")
      (value "100k")
      (footprint "eagle-import:R0603")
      (libsource (lib "eagle-import") (part "RESISTOR"))
    )
    (comp (ref "R93")
      (value "100k")
      (footprint "eagle-import:TRIMMER_64B")
      (libsource (lib "eagle-import") (part "TRIMMER64X"))
    )
    (comp (ref "R94")
      (value "47k")
      (footprint "eagle-import:R0603")
      (libsource (lib "eagle-import") (part "RESISTOR"))
    )
    (comp (ref "R95")
      (value "47k")
      (footprint "eagle-import:R0603")
      (libsource (lib "eagle-import") (part "RESISTOR"))
    )
    (comp (ref "R115")
      (value "2K")
      (footprint "eagle-import:R0603")
      (libsource (lib "eagle-import") (part "RESISTOR"))
    )
    (comp (ref "R116")
      (value "2K")
      (footprint "eagle-import:R0603")
      (libsource (lib "eagle-import") (part "RESISTOR"))
    )
    (comp (ref "SCK")
      (value "HEADER/MALE/01")
      (footprint "eagle-import:HEADER_MALE_01")
      (fields (field (name "SPICEPREFIX") "X"))
      (libsource (lib "eagle-import") (part "HEADER/MALE/01"))
    )
  )
  (nets
    (net (code "1") (name "+12V") (class "Default")
      (node (ref "+V") (pin "1") (pinfunction "3_1") (pintype "passive"))
      (node (ref "+V1") (pin "1") (pinfunction "3_1") (pintype "passive"))
      (node (ref "+V2") (pin "1") (pinfunction "3_1") (pintype "passive"))
      (node (ref "+V3") (pin "1") (pinfunction "3_1") (pintype "passive"))
      (node (ref "+V4") (pin "1") (pinfunction "3_1") (pintype "passive"))
      (node (ref "+V5") (pin "1") (pinfunction "3_1") (pintype "passive"))
      (node (ref "C1") (pin "+") (pinfunction "+_+") (pintype "passive"))
      (node (ref "C16") (pin "2") (pinfunction "2_2") (pintype "passive"))
      (node (ref "C23") (pin "2") (pinfunction "2_2") (pintype "passive"))
      (node (ref "C26") (pin "2") (pinfunction "2_2") (pintype "passive"))
      (node (ref "IC1") (pin "4") (pinfunction "V+_4") (pintype "power_in"))
      (node (ref "IC18") (pin "8") (pinfunction "V+_8") (pintype "power_in"))
      (node (ref "IC2") (pin "4") (pinfunction "V+_4") (pintype "power_in"))
      (node (ref "IC5") (pin "4") (pinfunction "V+_4") (pintype "power_in"))
      (node (ref "L1") (pin "1") (pinfunction "1_1") (pintype "passive"))
      (node (ref "L2") (pin "1") (pinfunction "1_1") (pintype "passive"))
    )
    (net (code "2") (name "-12V") (class "Default")
      (node (ref "-V") (pin "1") (pinfunction "3_1") (pintype "passive"))
      (node (ref "-V1") (pin "1") (pinfunction "3_1") (pintype "passive"))
      (node (ref "-V2") (pin "1") (pinfunction "3_1") (pintype "passive"))
      (node (ref "-V3") (pin "1") (pinfunction "3_1") (pintype "passive"))
      (node (ref "-V4") (pin "1") (pinfunction "3_1") (pintype "passive"))
      (node (ref "-V5") (pin "1") (pinfunction "3_1") (pintype "passive"))
      (node (ref "C17") (pin "1") (pinfunction "1_1") (pintype "passive"))
      (node (ref "C2") (pin "-") (pinfunction "-_-") (pintype "passive"))
      (node (ref "C24") (pin "1") (pinfunction "1_1") (pintype "passive"))
      (node (ref "C25") (pin "1") (pinfunction "1_1") (pintype "passive"))
      (node (ref "IC1") (pin "11") (pinfunction "V-_11") (pintype "power_in"))
      (node (ref "IC18") (pin "4") (pinfunction "V-_4") (pintype "power_in"))
      (node (ref "IC2") (pin "11") (pinfunction "V-_11") (pintype "power_in"))
      (node (ref "IC5") (pin "11") (pinfunction "V-_11") (pintype "power_in"))
      (node (ref "R7") (pin "2") (pinfunction "2_2") (pintype "passive"))
    )
    (net (code "3") (name "/-5VREF") (class "Default")
      (node (ref "-5V") (pin "1") (pinfunction "3_1") (pintype "passive"))
      (node (ref "-5V1") (pin "1") (pinfunction "3_1") (pintype "passive"))
      (node (ref "-5V2") (pin "1") (pinfunction "3_1") (pintype "passive"))
      (node (ref "-5V3") (pin "1") (pinfunction "3_1") (pintype "passive"))
      (node (ref "C6") (pin "2") (pinfunction "2_2") (pintype "passive"))
      (node (ref "IC8") (pin "2") (pinfunction "A_2") (pintype "output"))
      (node (ref "R13") (pin "1") (pinfunction "1_1") (pintype "passive"))
      (node (ref "R29") (pin "1") (pinfunction "1_1") (pintype "passive"))
      (node (ref "R67") (pin "1") (pinfunction "1_1") (pintype "passive"))
      (node (ref "R7") (pin "1") (pinfunction "1_1") (pintype "passive"))
      (node (ref "R71") (pin "1") (pinfunction "1_1") (pintype "passive"))
      (node (ref "R78") (pin "1") (pinfunction "1_1") (pintype "passive"))
      (node (ref "R79") (pin "1") (pinfunction "1_1") (pintype "passive"))
      (node (ref "R80") (pin "1") (pinfunction "1_1") (pintype "passive"))
      (node (ref "R81") (pin "1") (pinfunction "1_1") (pintype "passive"))
      (node (ref "R82") (pin "1") (pinfunction "1_1") (pintype "passive"))
      (node (ref "R83") (pin "1") (pinfunction "1_1") (pintype "passive"))
      (node (ref "R84") (pin "1") (pinfunction "1_1") (pintype "passive"))
      (node (ref "R85") (pin "1") (pinfunction "1_1") (pintype "passive"))
      (node (ref "R86") (pin "1") (pinfunction "1_1") (pintype "passive"))
      (node (ref "R87") (pin "1") (pinfunction "1_1") (pintype "passive"))
      (node (ref "R88") (pin "1") (pinfunction "1_1") (pintype "passive"))
      (node (ref "R89") (pin "1") (pinfunction "1_1") (pintype "passive"))
    )
    (net (code "4") (name "/A0") (class "Default")
      (node (ref "16_A0") (pin "1") (pinfunction "3_1") (pintype "passive"))
      (node (ref "IC6") (pin "14-A0/TX3/SPDIF_OUT") (pinfunction "14-A0/TX3/SPDIF_OUT_14-A0/TX3/SPDIF_OUT") (pintype "bidirectional"))
    )
    (net (code "5") (name "/A1") (class "Default")
      (node (ref "16_A1") (pin "1") (pinfunction "3_1") (pintype "passive"))
      (node (ref "IC6") (pin "15-A1/RX3/SPDIF_IN") (pinfunction "15-A1/RX3/SPDIF_IN_15-A1/RX3/SPDIF_IN") (pintype "bidirectional"))
    )
    (net (code "6") (name "/A2") (class "Default")
      (node (ref "16_A2") (pin "1") (pinfunction "3_1") (pintype "passive"))
      (node (ref "IC6") (pin "16-A2/RX4/SCL1") (pinfunction "16-A2/RX4/SCL1_16-A2/RX4/SCL1") (pintype "bidirectional"))
    )
    (net (code "7") (name "/A3") (class "Default")
      (node (ref "17_A3") (pin "1") (pinfunction "3_1") (pintype "passive"))
      (node (ref "IC6") (pin "17-A3/TX4/SDA1") (pinfunction "17-A3/TX4/SDA1_17-A3/TX4/SDA1") (pintype "bidirectional"))
    )
    (net (code "8") (name "/A6") (class "Default")
      (node (ref "C14") (pin "2") (pinfunction "2_2") (pintype "passive"))
      (node (ref "IC3") (pin "14") (pinfunction "OUT_14") (pintype "output"))
      (node (ref "IC6") (pin "20-A6/TX5/LRCLK1") (pinfunction "20-A6/TX5/LRCLK1_20-A6/TX5/LRCLK1") (pintype "bidirectional"))
      (node (ref "R68") (pin "2") (pinfunction "2_2") (pintype "passive"))
    )
    (net (code "9") (name "/A7") (class "Default")
      (node (ref "C7") (pin "2") (pinfunction "2_2") (pintype "passive"))
      (node (ref "IC3") (pin "1") (pinfunction "OUT_1") (pintype "output"))
      (node (ref "IC6") (pin "21-A7/RX5/BCLK1") (pinfunction "21-A7/RX5/BCLK1_21-A7/RX5/BCLK1") (pintype "bidirectional"))
      (node (ref "R8") (pin "2") (pinfunction "2_2") (pintype "passive"))
    )
    (net (code "10") (name "/A8") (class "Default")
      (node (ref "C10") (pin "2") (pinfunction "2_2") (pintype "passive"))
      (node (ref "IC3") (pin "7") (pinfunction "OUT_7") (pintype "output"))
      (node (ref "IC6") (pin "22-A8/CTX1") (pinfunction "22-A8/CTX1_22-A8/CTX1") (pintype "bidirectional"))
      (node (ref "R15") (pin "2") (pinfunction "2_2") (pintype "passive"))
    )
    (net (code "11") (name "/A9") (class "Default")
      (node (ref "C11") (pin "2") (pinfunction "2_2") (pintype "passive"))
      (node (ref "IC3") (pin "8") (pinfunction "OUT_8") (pintype "output"))
      (node (ref "IC6") (pin "23-A9/CRX1/MCLK1") (pinfunction "23-A9/CRX1/MCLK1_23-A9/CRX1/MCLK1") (pintype "bidirectional"))
      (node (ref "R64") (pin "2") (pinfunction "2_2") (pintype "passive"))
    )
    (net (code "12") (name "/A10") (class "Default")
      (node (ref "24_A10") (pin "1") (pinfunction "3_1") (pintype "passive"))
      (node (ref "IC6") (pin "24-A10/TX6/SCL2") (pinfunction "24-A10/TX6/SCL2_24-A10/TX6/SCL2") (pintype "bidirectional"))
    )
    (net (code "13") (name "/A11") (class "Default")
      (node (ref "25_A11") (pin "1") (pinfunction "3_1") (pintype "passive"))
      (node (ref "IC6") (pin "25-A11/RX6/SDA2") (pinfunction "25-A11/RX6/SDA2_25-A11/RX6/SDA2") (pintype "bidirectional"))
    )
    (net (code "14") (name "/A12") (class "Default")
      (node (ref "26_A12") (pin "1") (pinfunction "3_1") (pintype "passive"))
      (node (ref "IC6") (pin "26-A12/MOSI1") (pinfunction "26-A12/MOSI1_26-A12/MOSI1") (pintype "bidirectional"))
    )
    (net (code "15") (name "/A13") (class "Default")
      (node (ref "27_A13") (pin "1") (pinfunction "3_1") (pintype "passive"))
      (node (ref "IC6") (pin "27-A13/SCK1") (pinfunction "27-A13/SCK1_27-A13/SCK1") (pintype "bidirectional"))
    )
    (net (code "16") (name "/A14") (class "Default")
      (node (ref "38_A14") (pin "1") (pinfunction "3_1") (pintype "passive"))
      (node (ref "IC6") (pin "38-A14/CS/IN1") (pinfunction "38-A14/CS/IN1_38-A14/CS/IN1") (pintype "bidirectional"))
    )
    (net (code "17") (name "/A15") (class "Default")
      (node (ref "39_A15") (pin "1") (pinfunction "3_1") (pintype "passive"))
      (node (ref "IC6") (pin "39-A15/CS/OUT1A") (pinfunction "39-A15/CS/OUT1A_39-A15/CS/OUT1A") (pintype "bidirectional"))
    )
    (net (code "18") (name "/A16") (class "Default")
      (node (ref "40_A16") (pin "1") (pinfunction "3_1") (pintype "passive"))
      (node (ref "IC6") (pin "40-A16/CS1") (pinfunction "40-A16/CS1_40-A16/CS1") (pintype "bidirectional"))
    )
    (net (code "19") (name "/A17") (class "Default")
      (node (ref "41_A17") (pin "1") (pinfunction "3_1") (pintype "passive"))
      (node (ref "IC6") (pin "41-A17/MISO1") (pinfunction "41-A17/MISO1_41-A17/MISO1") (pintype "bidirectional"))
    )
    (net (code "20") (name "/IN1") (class "Default")
      (node (ref "C22") (pin "2") (pinfunction "2_2") (pintype "passive"))
      (node (ref "IC12") (pin "1") (pinfunction "P3A_1") (pintype "bidirectional"))
      (node (ref "IC12") (pin "20") (pinfunction "P2A_20") (pintype "bidirectional"))
      (node (ref "IC15") (pin "1") (pinfunction "P3A_1") (pintype "bidirectional"))
      (node (ref "IC15") (pin "20") (pinfunction "P2A_20") (pintype "bidirectional"))
      (node (ref "IC4") (pin "1") (pinfunction "P3A_1") (pintype "bidirectional"))
      (node (ref "IC4") (pin "20") (pinfunction "P2A_20") (pintype "bidirectional"))
      (node (ref "IC5") (pin "14") (pinfunction "OUT_14") (pintype "output"))
      (node (ref "R45") (pin "2") (pinfunction "2_2") (pintype "passive"))
    )
    (net (code "21") (name "/IN2") (class "Default")
      (node (ref "C12") (pin "2") (pinfunction "2_2") (pintype "passive"))
      (node (ref "IC12") (pin "10") (pinfunction "P1A_10") (pintype "bidirectional"))
      (node (ref "IC12") (pin "11") (pinfunction "P0A_11") (pintype "bidirectional"))
      (node (ref "IC15") (pin "10") (pinfunction "P1A_10") (pintype "bidirectional"))
      (node (ref "IC15") (pin "11") (pinfunction "P0A_11") (pintype "bidirectional"))
      (node (ref "IC4") (pin "10") (pinfunction "P1A_10") (pintype "bidirectional"))
      (node (ref "IC4") (pin "11") (pinfunction "P0A_11") (pintype "bidirectional"))
      (node (ref "IC5") (pin "1") (pinfunction "OUT_1") (pintype "output"))
      (node (ref "R19") (pin "2") (pinfunction "2_2") (pintype "passive"))
    )
    (net (code "22") (name "/IN3") (class "Default")
      (node (ref "C31") (pin "2") (pinfunction "2_2") (pintype "passive"))
      (node (ref "IC10") (pin "1") (pinfunction "P3A_1") (pintype "bidirectional"))
      (node (ref "IC10") (pin "20") (pinfunction "P2A_20") (pintype "bidirectional"))
      (node (ref "IC13") (pin "1") (pinfunction "P3A_1") (pintype "bidirectional"))
      (node (ref "IC13") (pin "20") (pinfunction "P2A_20") (pintype "bidirectional"))
      (node (ref "IC16") (pin "1") (pinfunction "P3A_1") (pintype "bidirectional"))
      (node (ref "IC16") (pin "20") (pinfunction "P2A_20") (pintype "bidirectional"))
      (node (ref "IC2") (pin "7") (pinfunction "OUT_7") (pintype "output"))
      (node (ref "R52") (pin "2") (pinfunction "2_2") (pintype "passive"))
    )
    (net (code "23") (name "/IN4") (class "Default")
      (node (ref "C20") (pin "2") (pinfunction "2_2") (pintype "passive"))
      (node (ref "IC10") (pin "10") (pinfunction "P1A_10") (pintype "bidirectional"))
      (node (ref "IC10") (pin "11") (pinfunction "P0A_11") (pintype "bidirectional"))
      (node (ref "IC13") (pin "10") (pinfunction "P1A_10") (pintype "bidirectional"))
      (node (ref "IC13") (pin "11") (pinfunction "P0A_11") (pintype "bidirectional"))
      (node (ref "IC16") (pin "10") (pinfunction "P1A_10") (pintype "bidirectional"))
      (node (ref "IC16") (pin "11") (pinfunction "P0A_11") (pintype "bidirectional"))
      (node (ref "IC2") (pin "8") (pinfunction "OUT_8") (pintype "output"))
      (node (ref "R47") (pin "2") (pinfunction "2_2") (pintype "passive"))
    )
    (net (code "24") (name "/IN5") (class "Default")
      (node (ref "C18") (pin "2") (pinfunction "2_2") (pintype "passive"))
      (node (ref "IC11") (pin "1") (pinfunction "P3A_1") (pintype "bidirectional"))
      (node (ref "IC11") (pin "20") (pinfunction "P2A_20") (pintype "bidirectional"))
      (node (ref "IC14") (pin "1") (pinfunction "P3A_1") (pintype "bidirectional"))
      (node (ref "IC14") (pin "20") (pinfunction "P2A_20") (pintype "bidirectional"))
      (node (ref "IC17") (pin "1") (pinfunction "P3A_1") (pintype "bidirectional"))
      (node (ref "IC17") (pin "20") (pinfunction "P2A_20") (pintype "bidirectional"))
      (node (ref "IC2") (pin "14") (pinfunction "OUT_14") (pintype "output"))
      (node (ref "R38") (pin "2") (pinfunction "2_2") (pintype "passive"))
    )
    (net (code "25") (name "/IN6") (class "Default")
      (node (ref "C21") (pin "2") (pinfunction "2_2") (pintype "passive"))
      (node (ref "IC11") (pin "10") (pinfunction "P1A_10") (pintype "bidirectional"))
      (node (ref "IC11") (pin "11") (pinfunction "P0A_11") (pintype "bidirectional"))
      (node (ref "IC14") (pin "10") (pinfunction "P1A_10") (pintype "bidirectional"))
      (node (ref "IC14") (pin "11") (pinfunction "P0A_11") (pintype "bidirectional"))
      (node (ref "IC17") (pin "10") (pinfunction "P1A_10") (pintype "bidirectional"))
      (node (ref "IC17") (pin "11") (pinfunction "P0A_11") (pintype "bidirectional"))
      (node (ref "IC2") (pin "1") (pinfunction "OUT_1") (pintype "output"))
      (node (ref "R55") (pin "2") (pinfunction "2_2") (pintype "passive"))
    )
    (net (code "26") (name "/OUT1") (class "Default")
      (node (ref "C9") (pin "1") (pinfunction "1_1") (pintype "passive"))
      (node (ref "IC1") (pin "13") (pinfunction "-IN_13") (pintype "input"))
      (node (ref "R10") (pin "1") (pinfunction "1_1") (pintype "passive"))
      (node (ref "R16") (pin "1") (pinfunction "1_1") (pintype "passive"))
      (node (ref "R17") (pin "1") (pinfunction "1_1") (pintype "passive"))
      (node (ref "R21") (pin "1") (pinfunction "1_1") (pintype "passive"))
      (node (ref "R22") (pin "1") (pinfunction "1_1") (pintype "passive"))
      (node (ref "R23") (pin "1") (pinfunction "1_1") (pintype "passive"))
      (node (ref "R24") (pin "1") (pinfunction "1_1") (pintype "passive"))
      (node (ref "R85") (pin "2") (pinfunction "2_2") (pintype "passive"))
    )
    (net (code "27") (name "/OUT2") (class "Default")
      (node (ref "C8") (pin "1") (pinfunction "1_1") (pintype "passive"))
      (node (ref "IC1") (pin "9") (pinfunction "-IN_9") (pintype "input"))
      (node (ref "R2") (pin "2") (pinfunction "2_2") (pintype "passive"))
      (node (ref "R25") (pin "2") (pinfunction "2_2") (pintype "passive"))
      (node (ref "R26") (pin "2") (pinfunction "2_2") (pintype "passive"))
      (node (ref "R27") (pin "2") (pinfunction "2_2") (pintype "passive"))
      (node (ref "R28") (pin "2") (pinfunction "2_2") (pintype "passive"))
      (node (ref "R5") (pin "2") (pinfunction "2_2") (pintype "passive"))
      (node (ref "R89") (pin "2") (pinfunction "2_2") (pintype "passive"))
      (node (ref "R9") (pin "1") (pinfunction "1_1") (pintype "passive"))
    )
    (net (code "28") (name "/OUT3") (class "Default")
      (node (ref "C13") (pin "1") (pinfunction "1_1") (pintype "passive"))
      (node (ref "IC5") (pin "6") (pinfunction "-IN_6") (pintype "input"))
      (node (ref "R30") (pin "1") (pinfunction "1_1") (pintype "passive"))
      (node (ref "R31") (pin "1") (pinfunction "1_1") (pintype "passive"))
      (node (ref "R32") (pin "1") (pinfunction "1_1") (pintype "passive"))
      (node (ref "R33") (pin "1") (pinfunction "1_1") (pintype "passive"))
      (node (ref "R34") (pin "1") (pinfunction "1_1") (pintype "passive"))
      (node (ref "R35") (pin "1") (pinfunction "1_1") (pintype "passive"))
      (node (ref "R39") (pin "1") (pinfunction "1_1") (pintype "passive"))
      (node (ref "R87") (pin "2") (pinfunction "2_2") (pintype "passive"))
    )
    (net (code "29") (name "/OUT4") (class "Default")
      (node (ref "C19") (pin "1") (pinfunction "1_1") (pintype "passive"))
      (node (ref "IC5") (pin "9") (pinfunction "-IN_9") (pintype "input"))
      (node (ref "R36") (pin "2") (pinfunction "2_2") (pintype "passive"))
      (node (ref "R37") (pin "2") (pinfunction "2_2") (pintype "passive"))
      (node (ref "R40") (pin "2") (pinfunction "2_2") (pintype "passive"))
      (node (ref "R42") (pin "1") (pinfunction "1_1") (pintype "passive"))
      (node (ref "R43") (pin "2") (pinfunction "2_2") (pintype "passive"))
      (node (ref "R48") (pin "2") (pinfunction "2_2") (pintype "passive"))
      (node (ref "R49") (pin "2") (pinfunction "2_2") (pintype "passive"))
      (node (ref "R88") (pin "2") (pinfunction "2_2") (pintype "passive"))
    )
    (net (code "30") (name "/OUT5") (class "Default")
      (node (ref "C5") (pin "1") (pinfunction "1_1") (pintype "passive"))
      (node (ref "IC1") (pin "6") (pinfunction "-IN_6") (pintype "input"))
      (node (ref "R4") (pin "1") (pinfunction "1_1") (pintype "passive"))
      (node (ref "R50") (pin "1") (pinfunction "1_1") (pintype "passive"))
      (node (ref "R51") (pin "1") (pinfunction "1_1") (pintype "passive"))
      (node (ref "R53") (pin "1") (pinfunction "1_1") (pintype "passive"))
      (node (ref "R54") (pin "1") (pinfunction "1_1") (pintype "passive"))
      (node (ref "R56") (pin "1") (pinfunction "1_1") (pintype "passive"))
      (node (ref "R57") (pin "1") (pinfunction "1_1") (pintype "passive"))
      (node (ref "R86") (pin "2") (pinfunction "2_2") (pintype "passive"))
    )
    (net (code "31") (name "/OUT6") (class "Default")
      (node (ref "C4") (pin "1") (pinfunction "1_1") (pintype "passive"))
      (node (ref "IC1") (pin "2") (pinfunction "-IN_2") (pintype "input"))
      (node (ref "R1") (pin "1") (pinfunction "1_1") (pintype "passive"))
      (node (ref "R58") (pin "2") (pinfunction "2_2") (pintype "passive"))
      (node (ref "R59") (pin "2") (pinfunction "2_2") (pintype "passive"))
      (node (ref "R60") (pin "2") (pinfunction "2_2") (pintype "passive"))
      (node (ref "R61") (pin "2") (pinfunction "2_2") (pintype "passive"))
      (node (ref "R72") (pin "2") (pinfunction "2_2") (pintype "passive"))
      (node (ref "R73") (pin "2") (pinfunction "2_2") (pintype "passive"))
      (node (ref "R84") (pin "2") (pinfunction "2_2") (pintype "passive"))
    )
    (net (code "32") (name "/POT_RESET") (class "Default")
      (node (ref "IC6") (pin "0-RX1/CS1/CRX2") (pinfunction "0-RX1/CS1/CRX2_0-RX1/CS1/CRX2") (pintype "bidirectional"))
    )
    (net (code "33") (name "/SDO") (class "Default")
      (node (ref "IC10") (pin "16") (pinfunction "SDO_16") (pintype "bidirectional"))
      (node (ref "IC11") (pin "16") (pinfunction "SDO_16") (pintype "bidirectional"))
      (node (ref "IC12") (pin "16") (pinfunction "SDO_16") (pintype "bidirectional"))
      (node (ref "IC13") (pin "16") (pinfunction "SDO_16") (pintype "bidirectional"))
      (node (ref "IC14") (pin "16") (pinfunction "SDO_16") (pintype "bidirectional"))
      (node (ref "IC15") (pin "16") (pinfunction "SDO_16") (pintype "bidirectional"))
      (node (ref "IC16") (pin "16") (pinfunction "SDO_16") (pintype "bidirectional"))
      (node (ref "IC17") (pin "16") (pinfunction "SDO_16") (pintype "bidirectional"))
      (node (ref "IC4") (pin "16") (pinfunction "SDO_16") (pintype "bidirectional"))
    )
    (net (code "34") (name "/SPI_CS") (class "Default")
      (node (ref "10_CS") (pin "1") (pinfunction "3_1") (pintype "passive"))
      (node (ref "CS") (pin "1") (pinfunction "3_1") (pintype "passive"))
      (node (ref "IC6") (pin "10-CS\\MQSR") (pinfunction "10-CS/MQSR_10-CS\\MQSR") (pintype "bidirectional"))
    )
    (net (code "35") (name "/SPI_CS1") (class "Default")
      (node (ref "IC4") (pin "4") (pinfunction "~{CS}_4") (pintype "bidirectional"))
      (node (ref "IC6") (pin "9-OUT1C") (pinfunction "9-OUT1C_9-OUT1C") (pintype "bidirectional"))
    )
    (net (code "36") (name "/SPI_CS2") (class "Default")
      (node (ref "IC10") (pin "4") (pinfunction "~{CS}_4") (pintype "bidirectional"))
      (node (ref "IC6") (pin "8-TX2/IN1") (pinfunction "8-TX2/IN1_8-TX2/IN1") (pintype "bidirectional"))
    )
    (net (code "37") (name "/SPI_CS3") (class "Default")
      (node (ref "IC11") (pin "4") (pinfunction "~{CS}_4") (pintype "bidirectional"))
      (node (ref "IC6") (pin "7-RX2/OUT1A") (pinfunction "7-RX2/OUT1A_7-RX2/OUT1A") (pintype "bidirectional"))
    )
    (net (code "38") (name "/SPI_CS4") (class "Default")
      (node (ref "IC12") (pin "4") (pinfunction "~{CS}_4") (pintype "bidirectional"))
      (node (ref "IC6") (pin "6-OUT1D") (pinfunction "6-OUT1D_6-OUT1D") (pintype "bidirectional"))
    )
    (net (code "39") (name "/SPI_CS5") (class "Default")
      (node (ref "IC13") (pin "4") (pinfunction "~{CS}_4") (pintype "bidirectional"))
      (node (ref "IC6") (pin "5-IN2") (pinfunction "5-IN2_5-IN2") (pintype "bidirectional"))
    )
    (net (code "40") (name "/SPI_CS6") (class "Default")
      (node (ref "IC14") (pin "4") (pinfunction "~{CS}_4") (pintype "bidirectional"))
      (node (ref "IC6") (pin "4-BCLK2") (pinfunction "4-BCLK2_4-BCLK2") (pintype "bidirectional"))
    )
    (net (code "41") (name "/SPI_CS7") (class "Default")
      (node (ref "IC15") (pin "4") (pinfunction "~{CS}_4") (pintype "bidirectional"))
      (node (ref "IC6") (pin "3-LRCLK2") (pinfunction "3-LRCLK2_3-LRCLK2") (pintype "bidirectional"))
    )
    (net (code "42") (name "/SPI_CS8") (class "Default")
      (node (ref "IC16") (pin "4") (pinfunction "~{CS}_4") (pintype "bidirectional"))
      (node (ref "IC6") (pin "2-OUT2") (pinfunction "2-OUT2_2-OUT2") (pintype "bidirectional"))
    )
    (net (code "43") (name "/SPI_CS9") (class "Default")
      (node (ref "IC17") (pin "4") (pinfunction "~{CS}_4") (pintype "bidirectional"))
      (node (ref "IC6") (pin "1-TX1/MISO1/CTX2") (pinfunction "1-TX1/MISO1/CTX2_1-TX1/MISO1/CTX2") (pintype "bidirectional"))
    )
    (net (code "44") (name "/SPI_MISO") (class "Default")
      (node (ref "12_MISO") (pin "1") (pinfunction "3_1") (pintype "passive"))
      (node (ref "IC6") (pin "12-MISO/MQSL") (pinfunction "12-MISO/MQSL_12-MISO/MQSL") (pintype "bidirectional"))
      (node (ref "MISO") (pin "1") (pinfunction "3_1") (pintype "passive"))
    )
    (net (code "45") (name "/SPI_MOSI") (class "Default")
      (node (ref "11_MOSI") (pin "1") (pinfunction "3_1") (pintype "passive"))
      (node (ref "IC10") (pin "6") (pinfunction "SDI_6") (pintype "bidirectional"))
      (node (ref "IC11") (pin "6") (pinfunction "SDI_6") (pintype "bidirectional"))
      (node (ref "IC12") (pin "6") (pinfunction "SDI_6") (pintype "bidirectional"))
      (node (ref "IC13") (pin "6") (pinfunction "SDI_6") (pintype "bidirectional"))
      (node (ref "IC14") (pin "6") (pinfunction "SDI_6") (pintype "bidirectional"))
      (node (ref "IC15") (pin "6") (pinfunction "SDI_6") (pintype "bidirectional"))
      (node (ref "IC16") (pin "6") (pinfunction "SDI_6") (pintype "bidirectional"))
      (node (ref "IC17") (pin "6") (pinfunction "SDI_6") (pintype "bidirectional"))
      (node (ref "IC4") (pin "6") (pinfunction "SDI_6") (pintype "bidirectional"))
      (node (ref "IC6") (pin "11-MOSI/CTX1") (pinfunction "11-MOSI/CTX1_11-MOSI/CTX1") (pintype "bidirectional"))
      (node (ref "MOSI") (pin "1") (pinfunction "3_1") (pintype "passive"))
    )
    (net (code "46") (name "/SPI_SCK") (class "Default")
      (node (ref "13_SCK") (pin "1") (pinfunction "3_1") (pintype "passive"))
      (node (ref "IC10") (pin "5") (pinfunction "SCK_5") (pintype "bidirectional"))
      (node (ref "IC11") (pin "5") (pinfunction "SCK_5") (pintype "bidirectional"))
      (node (ref "IC12") (pin "5") (pinfunction "SCK_5") (pintype "bidirectional"))
      (node (ref "IC13") (pin "5") (pinfunction "SCK_5") (pintype "bidirectional"))
      (node (ref "IC14") (pin "5") (pinfunction "SCK_5") (pintype "bidirectional"))
      (node (ref "IC15") (pin "5") (pinfunction "SCK_5") (pintype "bidirectional"))
      (node (ref "IC16") (pin "5") (pinfunction "SCK_5") (pintype "bidirectional"))
      (node (ref "IC17") (pin "5") (pinfunction "SCK_5") (pintype "bidirectional"))
      (node (ref "IC4") (pin "5") (pinfunction "SCK_5") (pintype "bidirectional"))
      (node (ref "IC6") (pin "13-SCK/LED") (pinfunction "13-SCK/LED_13-SCK/LED") (pintype "bidirectional"))
      (node (ref "SCK") (pin "1") (pinfunction "3_1") (pintype "passive"))
    )
    (net (code "47") (name "3.3V") (class "Default")
      (node (ref "3.3V") (pin "1") (pinfunction "3_1") (pintype "passive"))
      (node (ref "3.3V1") (pin "1") (pinfunction "3_1") (pintype "passive"))
      (node (ref "3.3V2") (pin "1") (pinfunction "3_1") (pintype "passive"))
      (node (ref "3.3V3") (pin "1") (pinfunction "3_1") (pintype "passive"))
      (node (ref "IC6") (pin "3V3-3") (pinfunction "3V3-3_3V3-3") (pintype "bidirectional"))
      (node (ref "R115") (pin "2") (pinfunction "2_2") (pintype "passive"))
      (node (ref "R116") (pin "2") (pinfunction "2_2") (pintype "passive"))
    )
    (net (code "48") (name "3.3V_A") (class "Default")
      (node (ref "3.3VA") (pin "1") (pinfunction "3_1") (pintype "passive"))
      (node (ref "3.3VA1") (pin "1") (pinfunction "3_1") (pintype "passive"))
      (node (ref "3.3VA2") (pin "1") (pinfunction "3_1") (pintype "passive"))
      (node (ref "3.3VA3") (pin "1") (pinfunction "3_1") (pintype "passive"))
      (node (ref "C15") (pin "2") (pinfunction "2_2") (pintype "passive"))
      (node (ref "C30") (pin "+") (pinfunction "+_+") (pintype "passive"))
      (node (ref "IC3") (pin "4") (pinfunction "V+_4") (pintype "power_in"))
      (node (ref "IC9") (pin "1") (pinfunction "VOUT_1") (pintype "power_in"))
    )
    (net (code "49") (name "5V") (class "Default")
      (node (ref "5V") (pin "1") (pinfunction "3_1") (pintype "passive"))
      (node (ref "5V1") (pin "1") (pinfunction "3_1") (pintype "passive"))
      (node (ref "5V2") (pin "1") (pinfunction "3_1") (pintype "passive"))
      (node (ref "5V3") (pin "1") (pinfunction "3_1") (pintype "passive"))
      (node (ref "C27") (pin "2") (pinfunction "2_2") (pintype "passive"))
      (node (ref "C3") (pin "+") (pinfunction "+_+") (pintype "passive"))
      (node (ref "IC10") (pin "17") (pinfunction "VDD_17") (pintype "bidirectional"))
      (node (ref "IC11") (pin "17") (pinfunction "VDD_17") (pintype "bidirectional"))
      (node (ref "IC12") (pin "17") (pinfunction "VDD_17") (pintype "bidirectional"))
      (node (ref "IC13") (pin "17") (pinfunction "VDD_17") (pintype "bidirectional"))
      (node (ref "IC14") (pin "17") (pinfunction "VDD_17") (pintype "bidirectional"))
      (node (ref "IC15") (pin "17") (pinfunction "VDD_17") (pintype "bidirectional"))
      (node (ref "IC16") (pin "17") (pinfunction "VDD_17") (pintype "bidirectional"))
      (node (ref "IC17") (pin "17") (pinfunction "VDD_17") (pintype "bidirectional"))
      (node (ref "IC4") (pin "17") (pinfunction "VDD_17") (pintype "bidirectional"))
      (node (ref "IC6") (pin "VIN") (pinfunction "VIN_VIN") (pintype "bidirectional"))
      (node (ref "IC7") (pin "3") (pinfunction "VO_3") (pintype "passive"))
      (node (ref "R94") (pin "2") (pinfunction "2_2") (pintype "passive"))
    )
    (net (code "50") (name "GND") (class "Default")
      (node (ref "C1") (pin "-") (pinfunction "-_-") (pintype "passive"))
      (node (ref "C15") (pin "1") (pinfunction "1_1") (pintype "passive"))
      (node (ref "C16") (pin "1") (pinfunction "1_1") (pintype "passive"))
      (node (ref "C17") (pin "2") (pinfunction "2_2") (pintype "passive"))
      (node (ref "C2") (pin "+") (pinfunction "+_+") (pintype "passive"))
      (node (ref "C23") (pin "1") (pinfunction "1_1") (pintype "passive"))
      (node (ref "C24") (pin "2") (pinfunction "2_2") (pintype "passive"))
      (node (ref "C25") (pin "2") (pinfunction "2_2") (pintype "passive"))
      (node (ref "C26") (pin "1") (pinfunction "1_1") (pintype "passive"))
      (node (ref "C27") (pin "1") (pinfunction "1_1") (pintype "passive"))
      (node (ref "C28") (pin "1") (pinfunction "1_1") (pintype "passive"))
      (node (ref "C29") (pin "1") (pinfunction "1_1") (pintype "passive"))
      (node (ref "C3") (pin "-") (pinfunction "-_-") (pintype "passive"))
      (node (ref "C30") (pin "-") (pinfunction "-_-") (pintype "passive"))
      (node (ref "C6") (pin "1") (pinfunction "1_1") (pintype "passive"))
      (node (ref "GND") (pin "1") (pinfunction "3_1") (pintype "passive"))
      (node (ref "GND1") (pin "1") (pinfunction "3_1") (pintype "passive"))
      (node (ref "GND10") (pin "1") (pinfunction "3_1") (pintype "passive"))
      (node (ref "GND11") (pin "1") (pinfunction "3_1") (pintype "passive"))
      (node (ref "GND2") (pin "1") (pinfunction "3_1") (pintype "passive"))
      (node (ref "GND3") (pin "1") (pinfunction "3_1") (pintype "passive"))
      (node (ref "GND4") (pin "1") (pinfunction "3_1") (pintype "passive"))
      (node (ref "GND5") (pin "1") (pinfunction "3_1") (pintype "passive"))
      (node (ref "GND6") (pin "1") (pinfunction "3_1") (pintype "passive"))
      (node (ref "GND7") (pin "1") (pinfunction "3_1") (pintype "passive"))
      (node (ref "GND8") (pin "1") (pinfunction "3_1") (pintype "passive"))
      (node (ref "GND9") (pin "1") (pinfunction "3_1") (pintype "passive"))
      (node (ref "IC1") (pin "10") (pinfunction "+IN_10") (pintype "input"))
      (node (ref "IC1") (pin "12") (pinfunction "+IN_12") (pintype "input"))
      (node (ref "IC1") (pin "3") (pinfunction "+IN_3") (pintype "input"))
      (node (ref "IC1") (pin "5") (pinfunction "+IN_5") (pintype "input"))
      (node (ref "IC10") (pin "7") (pinfunction "VSS_7") (pintype "bidirectional"))
      (node (ref "IC11") (pin "7") (pinfunction "VSS_7") (pintype "bidirectional"))
      (node (ref "IC12") (pin "7") (pinfunction "VSS_7") (pintype "bidirectional"))
      (node (ref "IC13") (pin "7") (pinfunction "VSS_7") (pintype "bidirectional"))
      (node (ref "IC14") (pin "7") (pinfunction "VSS_7") (pintype "bidirectional"))
      (node (ref "IC15") (pin "7") (pinfunction "VSS_7") (pintype "bidirectional"))
      (node (ref "IC16") (pin "7") (pinfunction "VSS_7") (pintype "bidirectional"))
      (node (ref "IC17") (pin "7") (pinfunction "VSS_7") (pintype "bidirectional"))
      (node (ref "IC18") (pin "5") (pinfunction "+IN_5") (pintype "input"))
      (node (ref "IC2") (pin "10") (pinfunction "+IN_10") (pintype "input"))
      (node (ref "IC2") (pin "12") (pinfunction "+IN_12") (pintype "input"))
      (node (ref "IC2") (pin "3") (pinfunction "+IN_3") (pintype "input"))
      (node (ref "IC2") (pin "5") (pinfunction "+IN_5") (pintype "input"))
      (node (ref "IC3") (pin "10") (pinfunction "+IN_10") (pintype "input"))
      (node (ref "IC3") (pin "11") (pinfunction "V-_11") (pintype "power_in"))
      (node (ref "IC3") (pin "12") (pinfunction "+IN_12") (pintype "input"))
      (node (ref "IC3") (pin "3") (pinfunction "+IN_3") (pintype "input"))
      (node (ref "IC3") (pin "5") (pinfunction "+IN_5") (pintype "input"))
      (node (ref "IC4") (pin "7") (pinfunction "VSS_7") (pintype "bidirectional"))
      (node (ref "IC5") (pin "10") (pinfunction "+IN_10") (pintype "input"))
      (node (ref "IC5") (pin "12") (pinfunction "+IN_12") (pintype "input"))
      (node (ref "IC5") (pin "3") (pinfunction "+IN_3") (pintype "input"))
      (node (ref "IC5") (pin "5") (pinfunction "+IN_5") (pintype "input"))
      (node (ref "IC6") (pin "GND1") (pinfunction "GND1_GND1") (pintype "bidirectional"))
      (node (ref "IC6") (pin "GND3") (pinfunction "GND3_GND3") (pintype "bidirectional"))
      (node (ref "IC6") (pin "GND6") (pinfunction "GND6_GND6") (pintype "bidirectional"))
      (node (ref "IC7") (pin "2") (pinfunction "GND_2") (pintype "passive"))
      (node (ref "IC8") (pin "1") (pinfunction "C_1") (pintype "input"))
      (node (ref "IC9") (pin "2") (pinfunction "GND_2") (pintype "power_in"))
      (node (ref "IC9") (pin "2-2") (pinfunction "GND_2-2") (pintype "power_in"))
      (node (ref "R95") (pin "1") (pinfunction "1_1") (pintype "passive"))
    )
    (net (code "51") (name "Net-(18_A4_SDA-3)") (class "Default")
      (node (ref "18_A4_SDA") (pin "1") (pinfunction "3_1") (pintype "passive"))
      (node (ref "IC6") (pin "18-A4/SDA0") (pinfunction "18-A4/SDA0_18-A4/SDA0") (pintype "bidirectional"))
      (node (ref "R115") (pin "1") (pinfunction "1_1") (pintype "passive"))
    )
    (net (code "52") (name "Net-(19_A5_SCL-3)") (class "Default")
      (node (ref "19_A5_SCL") (pin "1") (pinfunction "3_1") (pintype "passive"))
      (node (ref "IC6") (pin "19-A5/SCL0") (pinfunction "19-A5/SCL0_19-A5/SCL0") (pintype "bidirectional"))
      (node (ref "R116") (pin "1") (pinfunction "1_1") (pintype "passive"))
    )
    (net (code "53") (name "Net-(28-3)") (class "Default")
      (node (ref "28") (pin "1") (pinfunction "3_1") (pintype "passive"))
      (node (ref "IC6") (pin "28-RX7") (pinfunction "28-RX7_28-RX7") (pintype "bidirectional"))
    )
    (net (code "54") (name "Net-(29-3)") (class "Default")
      (node (ref "29") (pin "1") (pinfunction "3_1") (pintype "passive"))
      (node (ref "IC6") (pin "29-TX7") (pinfunction "29-TX7_29-TX7") (pintype "bidirectional"))
    )
    (net (code "55") (name "Net-(30-3)") (class "Default")
      (node (ref "30") (pin "1") (pinfunction "3_1") (pintype "passive"))
      (node (ref "IC6") (pin "30-CRX3") (pinfunction "30-CRX3_30-CRX3") (pintype "bidirectional"))
    )
    (net (code "56") (name "Net-(31-3)") (class "Default")
      (node (ref "31") (pin "1") (pinfunction "3_1") (pintype "passive"))
      (node (ref "IC6") (pin "31-CTX3") (pinfunction "31-CTX3_31-CTX3") (pintype "bidirectional"))
    )
    (net (code "57") (name "Net-(32-3)") (class "Default")
      (node (ref "32") (pin "1") (pinfunction "3_1") (pintype "passive"))
      (node (ref "IC6") (pin "32-OUT1B") (pinfunction "32-OUT1B_32-OUT1B") (pintype "bidirectional"))
    )
    (net (code "58") (name "Net-(33-3)") (class "Default")
      (node (ref "33") (pin "1") (pinfunction "3_1") (pintype "passive"))
      (node (ref "IC6") (pin "33-MCLK2") (pinfunction "33-MCLK2_33-MCLK2") (pintype "bidirectional"))
    )
    (net (code "59") (name "Net-(34-3)") (class "Default")
      (node (ref "34") (pin "1") (pinfunction "3_1") (pintype "passive"))
      (node (ref "IC6") (pin "34-RX8") (pinfunction "34-RX8_34-RX8") (pintype "bidirectional"))
    )
    (net (code "60") (name "Net-(35-3)") (class "Default")
      (node (ref "35") (pin "1") (pinfunction "3_1") (pintype "passive"))
      (node (ref "IC6") (pin "35-TX8") (pinfunction "35/TX8_35-TX8") (pintype "bidirectional"))
    )
    (net (code "61") (name "Net-(36-3)") (class "Default")
      (node (ref "36") (pin "1") (pinfunction "3_1") (pintype "passive"))
      (node (ref "IC6") (pin "36-PWM") (pinfunction "36-PWM_36-PWM") (pintype "bidirectional"))
    )
    (net (code "62") (name "Net-(37-3)") (class "Default")
      (node (ref "37") (pin "1") (pinfunction "3_1") (pintype "passive"))
      (node (ref "IC6") (pin "37-PWM") (pinfunction "37-PWM_37-PWM") (pintype "bidirectional"))
    )
    (net (code "63") (name "Net-(CV5-3)") (class "Default")
      (node (ref "CV5") (pin "1") (pinfunction "3_1") (pintype "passive"))
      (node (ref "R65") (pin "1") (pinfunction "1_1") (pintype "passive"))
    )
    (net (code "64") (name "Net-(CV5B-3)") (class "Default")
      (node (ref "CV5B") (pin "1") (pinfunction "3_1") (pintype "passive"))
      (node (ref "R66") (pin "1") (pinfunction "1_1") (pintype "passive"))
    )
    (net (code "65") (name "Net-(CV6-3)") (class "Default")
      (node (ref "CV6") (pin "1") (pinfunction "3_1") (pintype "passive"))
      (node (ref "R62") (pin "1") (pinfunction "1_1") (pintype "passive"))
    )
    (net (code "66") (name "Net-(CV6B-3)") (class "Default")
      (node (ref "CV6B") (pin "1") (pinfunction "3_1") (pintype "passive"))
      (node (ref "R63") (pin "1") (pinfunction "1_1") (pintype "passive"))
    )
    (net (code "67") (name "Net-(CV7-3)") (class "Default")
      (node (ref "CV7") (pin "1") (pinfunction "3_1") (pintype "passive"))
      (node (ref "R11") (pin "1") (pinfunction "1_1") (pintype "passive"))
    )
    (net (code "68") (name "Net-(CV7B-3)") (class "Default")
      (node (ref "CV7B") (pin "1") (pinfunction "3_1") (pintype "passive"))
      (node (ref "R12") (pin "1") (pinfunction "1_1") (pintype "passive"))
    )
    (net (code "69") (name "Net-(CV8-3)") (class "Default")
      (node (ref "CV8") (pin "1") (pinfunction "3_1") (pintype "passive"))
      (node (ref "R69") (pin "1") (pinfunction "1_1") (pintype "passive"))
    )
    (net (code "70") (name "Net-(CV8B-3)") (class "Default")
      (node (ref "CV8B") (pin "1") (pinfunction "3_1") (pintype "passive"))
      (node (ref "R70") (pin "1") (pinfunction "1_1") (pintype "passive"))
    )
    (net (code "71") (name "Net-(IC1A-OUT)") (class "Default")
      (node (ref "C4") (pin "2") (pinfunction "2_2") (pintype "passive"))
      (node (ref "IC1") (pin "1") (pinfunction "OUT_1") (pintype "output"))
      (node (ref "R3") (pin "1") (pinfunction "1_1") (pintype "passive"))
    )
    (net (code "72") (name "Net-(IC1B-OUT)") (class "Default")
      (node (ref "C5") (pin "2") (pinfunction "2_2") (pintype "passive"))
      (node (ref "IC1") (pin "7") (pinfunction "OUT_7") (pintype "output"))
      (node (ref "R6") (pin "1") (pinfunction "1_1") (pintype "passive"))
    )
    (net (code "73") (name "Net-(IC1C-OUT)") (class "Default")
      (node (ref "C8") (pin "2") (pinfunction "2_2") (pintype "passive"))
      (node (ref "IC1") (pin "8") (pinfunction "OUT_8") (pintype "output"))
      (node (ref "R14") (pin "1") (pinfunction "1_1") (pintype "passive"))
    )
    (net (code "74") (name "Net-(IC1D-OUT)") (class "Default")
      (node (ref "C9") (pin "2") (pinfunction "2_2") (pintype "passive"))
      (node (ref "IC1") (pin "14") (pinfunction "OUT_14") (pintype "output"))
      (node (ref "R18") (pin "1") (pinfunction "1_1") (pintype "passive"))
    )
    (net (code "75") (name "Net-(IC2A--IN)") (class "Default")
      (node (ref "C21") (pin "1") (pinfunction "1_1") (pintype "passive"))
      (node (ref "IC2") (pin "2") (pinfunction "-IN_2") (pintype "input"))
      (node (ref "R55") (pin "1") (pinfunction "1_1") (pintype "passive"))
      (node (ref "R74") (pin "2") (pinfunction "2_2") (pintype "passive"))
      (node (ref "R79") (pin "2") (pinfunction "2_2") (pintype "passive"))
    )
    (net (code "76") (name "Net-(IC2B--IN)") (class "Default")
      (node (ref "C31") (pin "1") (pinfunction "1_1") (pintype "passive"))
      (node (ref "IC2") (pin "6") (pinfunction "-IN_6") (pintype "input"))
      (node (ref "R52") (pin "1") (pinfunction "1_1") (pintype "passive"))
      (node (ref "R75") (pin "2") (pinfunction "2_2") (pintype "passive"))
      (node (ref "R78") (pin "2") (pinfunction "2_2") (pintype "passive"))
    )
    (net (code "77") (name "Net-(IC2C--IN)") (class "Default")
      (node (ref "C20") (pin "1") (pinfunction "1_1") (pintype "passive"))
      (node (ref "IC2") (pin "9") (pinfunction "-IN_9") (pintype "input"))
      (node (ref "R47") (pin "1") (pinfunction "1_1") (pintype "passive"))
      (node (ref "R76") (pin "2") (pinfunction "2_2") (pintype "passive"))
      (node (ref "R80") (pin "2") (pinfunction "2_2") (pintype "passive"))
    )
    (net (code "78") (name "Net-(IC2D--IN)") (class "Default")
      (node (ref "C18") (pin "1") (pinfunction "1_1") (pintype "passive"))
      (node (ref "IC2") (pin "13") (pinfunction "-IN_13") (pintype "input"))
      (node (ref "R38") (pin "1") (pinfunction "1_1") (pintype "passive"))
      (node (ref "R77") (pin "2") (pinfunction "2_2") (pintype "passive"))
      (node (ref "R82") (pin "2") (pinfunction "2_2") (pintype "passive"))
    )
    (net (code "79") (name "Net-(IC3A--IN)") (class "Default")
      (node (ref "C7") (pin "1") (pinfunction "1_1") (pintype "passive"))
      (node (ref "IC3") (pin "2") (pinfunction "-IN_2") (pintype "input"))
      (node (ref "R11") (pin "2") (pinfunction "2_2") (pintype "passive"))
      (node (ref "R12") (pin "2") (pinfunction "2_2") (pintype "passive"))
      (node (ref "R13") (pin "2") (pinfunction "2_2") (pintype "passive"))
      (node (ref "R8") (pin "1") (pinfunction "1_1") (pintype "passive"))
    )
    (net (code "80") (name "Net-(IC3B--IN)") (class "Default")
      (node (ref "C10") (pin "1") (pinfunction "1_1") (pintype "passive"))
      (node (ref "IC3") (pin "6") (pinfunction "-IN_6") (pintype "input"))
      (node (ref "R15") (pin "1") (pinfunction "1_1") (pintype "passive"))
      (node (ref "R29") (pin "2") (pinfunction "2_2") (pintype "passive"))
      (node (ref "R62") (pin "2") (pinfunction "2_2") (pintype "passive"))
      (node (ref "R63") (pin "2") (pinfunction "2_2") (pintype "passive"))
    )
    (net (code "81") (name "Net-(IC3C--IN)") (class "Default")
      (node (ref "C11") (pin "1") (pinfunction "1_1") (pintype "passive"))
      (node (ref "IC3") (pin "9") (pinfunction "-IN_9") (pintype "input"))
      (node (ref "R64") (pin "1") (pinfunction "1_1") (pintype "passive"))
      (node (ref "R65") (pin "2") (pinfunction "2_2") (pintype "passive"))
      (node (ref "R66") (pin "2") (pinfunction "2_2") (pintype "passive"))
      (node (ref "R67") (pin "2") (pinfunction "2_2") (pintype "passive"))
    )
    (net (code "82") (name "Net-(IC3D--IN)") (class "Default")
      (node (ref "C14") (pin "1") (pinfunction "1_1") (pintype "passive"))
      (node (ref "IC3") (pin "13") (pinfunction "-IN_13") (pintype "input"))
      (node (ref "R68") (pin "1") (pinfunction "1_1") (pintype "passive"))
      (node (ref "R69") (pin "2") (pinfunction "2_2") (pintype "passive"))
      (node (ref "R70") (pin "2") (pinfunction "2_2") (pintype "passive"))
      (node (ref "R71") (pin "2") (pinfunction "2_2") (pintype "passive"))
    )
    (net (code "83") (name "Net-(IC4-P0W)") (class "Default")
      (node (ref "IC4") (pin "12") (pinfunction "P0W_12") (pintype "bidirectional"))
      (node (ref "R2") (pin "1") (pinfunction "1_1") (pintype "passive"))
    )
    (net (code "84") (name "Net-(IC4-P1W)") (class "Default")
      (node (ref "IC4") (pin "9") (pinfunction "P1W_9") (pintype "bidirectional"))
      (node (ref "R17") (pin "2") (pinfunction "2_2") (pintype "passive"))
    )
    (net (code "85") (name "Net-(IC4-P2W)") (class "Default")
      (node (ref "IC4") (pin "19") (pinfunction "P2W_19") (pintype "bidirectional"))
      (node (ref "R5") (pin "1") (pinfunction "1_1") (pintype "passive"))
    )
    (net (code "86") (name "Net-(IC4-P3W)") (class "Default")
      (node (ref "IC4") (pin "2") (pinfunction "P3W_2") (pintype "bidirectional"))
      (node (ref "R10") (pin "2") (pinfunction "2_2") (pintype "passive"))
    )
    (net (code "87") (name "Net-(IC5A--IN)") (class "Default")
      (node (ref "C12") (pin "1") (pinfunction "1_1") (pintype "passive"))
      (node (ref "IC5") (pin "2") (pinfunction "-IN_2") (pintype "input"))
      (node (ref "R19") (pin "1") (pinfunction "1_1") (pintype "passive"))
      (node (ref "R20") (pin "2") (pinfunction "2_2") (pintype "passive"))
      (node (ref "R81") (pin "2") (pinfunction "2_2") (pintype "passive"))
    )
    (net (code "88") (name "Net-(IC5B-OUT)") (class "Default")
      (node (ref "C13") (pin "2") (pinfunction "2_2") (pintype "passive"))
      (node (ref "IC5") (pin "7") (pinfunction "OUT_7") (pintype "output"))
      (node (ref "R41") (pin "1") (pinfunction "1_1") (pintype "passive"))
    )
    (net (code "89") (name "Net-(IC5C-OUT)") (class "Default")
      (node (ref "C19") (pin "2") (pinfunction "2_2") (pintype "passive"))
      (node (ref "IC5") (pin "8") (pinfunction "OUT_8") (pintype "output"))
      (node (ref "R44") (pin "1") (pinfunction "1_1") (pintype "passive"))
    )
    (net (code "90") (name "Net-(IC5D--IN)") (class "Default")
      (node (ref "C22") (pin "1") (pinfunction "1_1") (pintype "passive"))
      (node (ref "IC5") (pin "13") (pinfunction "-IN_13") (pintype "input"))
      (node (ref "R45") (pin "1") (pinfunction "1_1") (pintype "passive"))
      (node (ref "R46") (pin "2") (pinfunction "2_2") (pintype "passive"))
      (node (ref "R83") (pin "2") (pinfunction "2_2") (pintype "passive"))
    )
    (net (code "91") (name "Net-(IC7-VI)") (class "Default")
      (node (ref "C28") (pin "2") (pinfunction "2_2") (pintype "passive"))
      (node (ref "IC7") (pin "1") (pinfunction "VI_1") (pintype "input"))
      (node (ref "L1") (pin "2") (pinfunction "2_2") (pintype "passive"))
    )
    (net (code "92") (name "Net-(IC9-VIN)") (class "Default")
      (node (ref "C29") (pin "2") (pinfunction "2_2") (pintype "passive"))
      (node (ref "IC9") (pin "3") (pinfunction "VIN_3") (pintype "power_in"))
      (node (ref "L2") (pin "2") (pinfunction "2_2") (pintype "passive"))
    )
    (net (code "93") (name "Net-(IC10-P0B)") (class "Default")
      (node (ref "IC10") (pin "13") (pinfunction "P0B_13") (pintype "bidirectional"))
      (node (ref "IC10") (pin "18") (pinfunction "P2B_18") (pintype "bidirectional"))
      (node (ref "IC10") (pin "3") (pinfunction "P3B_3") (pintype "bidirectional"))
      (node (ref "IC10") (pin "8") (pinfunction "P1B_8") (pintype "bidirectional"))
      (node (ref "IC11") (pin "13") (pinfunction "P0B_13") (pintype "bidirectional"))
      (node (ref "IC11") (pin "18") (pinfunction "P2B_18") (pintype "bidirectional"))
      (node (ref "IC11") (pin "3") (pinfunction "P3B_3") (pintype "bidirectional"))
      (node (ref "IC11") (pin "8") (pinfunction "P1B_8") (pintype "bidirectional"))
      (node (ref "IC12") (pin "13") (pinfunction "P0B_13") (pintype "bidirectional"))
      (node (ref "IC12") (pin "18") (pinfunction "P2B_18") (pintype "bidirectional"))
      (node (ref "IC12") (pin "3") (pinfunction "P3B_3") (pintype "bidirectional"))
      (node (ref "IC12") (pin "8") (pinfunction "P1B_8") (pintype "bidirectional"))
      (node (ref "IC13") (pin "13") (pinfunction "P0B_13") (pintype "bidirectional"))
      (node (ref "IC13") (pin "18") (pinfunction "P2B_18") (pintype "bidirectional"))
      (node (ref "IC13") (pin "3") (pinfunction "P3B_3") (pintype "bidirectional"))
      (node (ref "IC13") (pin "8") (pinfunction "P1B_8") (pintype "bidirectional"))
      (node (ref "IC14") (pin "13") (pinfunction "P0B_13") (pintype "bidirectional"))
      (node (ref "IC14") (pin "18") (pinfunction "P2B_18") (pintype "bidirectional"))
      (node (ref "IC14") (pin "3") (pinfunction "P3B_3") (pintype "bidirectional"))
      (node (ref "IC14") (pin "8") (pinfunction "P1B_8") (pintype "bidirectional"))
      (node (ref "IC15") (pin "13") (pinfunction "P0B_13") (pintype "bidirectional"))
      (node (ref "IC15") (pin "18") (pinfunction "P2B_18") (pintype "bidirectional"))
      (node (ref "IC15") (pin "3") (pinfunction "P3B_3") (pintype "bidirectional"))
      (node (ref "IC15") (pin "8") (pinfunction "P1B_8") (pintype "bidirectional"))
      (node (ref "IC16") (pin "13") (pinfunction "P0B_13") (pintype "bidirectional"))
      (node (ref "IC16") (pin "18") (pinfunction "P2B_18") (pintype "bidirectional"))
      (node (ref "IC16") (pin "3") (pinfunction "P3B_3") (pintype "bidirectional"))
      (node (ref "IC16") (pin "8") (pinfunction "P1B_8") (pintype "bidirectional"))
      (node (ref "IC17") (pin "13") (pinfunction "P0B_13") (pintype "bidirectional"))
      (node (ref "IC17") (pin "18") (pinfunction "P2B_18") (pintype "bidirectional"))
      (node (ref "IC17") (pin "3") (pinfunction "P3B_3") (pintype "bidirectional"))
      (node (ref "IC17") (pin "8") (pinfunction "P1B_8") (pintype "bidirectional"))
      (node (ref "IC18") (pin "1") (pinfunction "OUT_1") (pintype "output"))
      (node (ref "IC18") (pin "2") (pinfunction "-IN_2") (pintype "input"))
      (node (ref "IC4") (pin "13") (pinfunction "P0B_13") (pintype "bidirectional"))
      (node (ref "IC4") (pin "18") (pinfunction "P2B_18") (pintype "bidirectional"))
      (node (ref "IC4") (pin "3") (pinfunction "P3B_3") (pintype "bidirectional"))
      (node (ref "IC4") (pin "8") (pinfunction "P1B_8") (pintype "bidirectional"))
    )
    (net (code "94") (name "Net-(IC10-P0W)") (class "Default")
      (node (ref "IC10") (pin "12") (pinfunction "P0W_12") (pintype "bidirectional"))
      (node (ref "R27") (pin "1") (pinfunction "1_1") (pintype "passive"))
    )
    (net (code "95") (name "Net-(IC10-P1W)") (class "Default")
      (node (ref "IC10") (pin "9") (pinfunction "P1W_9") (pintype "bidirectional"))
      (node (ref "R22") (pin "2") (pinfunction "2_2") (pintype "passive"))
    )
    (net (code "96") (name "Net-(IC10-P2W)") (class "Default")
      (node (ref "IC10") (pin "19") (pinfunction "P2W_19") (pintype "bidirectional"))
      (node (ref "R28") (pin "1") (pinfunction "1_1") (pintype "passive"))
    )
    (net (code "97") (name "Net-(IC10-P3W)") (class "Default")
      (node (ref "IC10") (pin "2") (pinfunction "P3W_2") (pintype "bidirectional"))
      (node (ref "R21") (pin "2") (pinfunction "2_2") (pintype "passive"))
    )
    (net (code "98") (name "Net-(IC11-P0W)") (class "Default")
      (node (ref "IC11") (pin "12") (pinfunction "P0W_12") (pintype "bidirectional"))
      (node (ref "R25") (pin "1") (pinfunction "1_1") (pintype "passive"))
    )
    (net (code "99") (name "Net-(IC11-P1W)") (class "Default")
      (node (ref "IC11") (pin "9") (pinfunction "P1W_9") (pintype "bidirectional"))
      (node (ref "R24") (pin "2") (pinfunction "2_2") (pintype "passive"))
    )
    (net (code "100") (name "Net-(IC11-P2W)") (class "Default")
      (node (ref "IC11") (pin "19") (pinfunction "P2W_19") (pintype "bidirectional"))
      (node (ref "R26") (pin "1") (pinfunction "1_1") (pintype "passive"))
    )
    (net (code "101") (name "Net-(IC11-P3W)") (class "Default")
      (node (ref "IC11") (pin "2") (pinfunction "P3W_2") (pintype "bidirectional"))
      (node (ref "R23") (pin "2") (pinfunction "2_2") (pintype "passive"))
    )
    (net (code "102") (name "Net-(IC12-P0W)") (class "Default")
      (node (ref "IC12") (pin "12") (pinfunction "P0W_12") (pintype "bidirectional"))
      (node (ref "R37") (pin "1") (pinfunction "1_1") (pintype "passive"))
    )
    (net (code "103") (name "Net-(IC12-P1W)") (class "Default")
      (node (ref "IC12") (pin "9") (pinfunction "P1W_9") (pintype "bidirectional"))
      (node (ref "R31") (pin "2") (pinfunction "2_2") (pintype "passive"))
    )
    (net (code "104") (name "Net-(IC12-P2W)") (class "Default")
      (node (ref "IC12") (pin "19") (pinfunction "P2W_19") (pintype "bidirectional"))
      (node (ref "R36") (pin "1") (pinfunction "1_1") (pintype "passive"))
    )
    (net (code "105") (name "Net-(IC12-P3W)") (class "Default")
      (node (ref "IC12") (pin "2") (pinfunction "P3W_2") (pintype "bidirectional"))
      (node (ref "R30") (pin "2") (pinfunction "2_2") (pintype "passive"))
    )
    (net (code "106") (name "Net-(IC13-P0W)") (class "Default")
      (node (ref "IC13") (pin "12") (pinfunction "P0W_12") (pintype "bidirectional"))
      (node (ref "R43") (pin "1") (pinfunction "1_1") (pintype "passive"))
    )
    (net (code "107") (name "Net-(IC13-P1W)") (class "Default")
      (node (ref "IC13") (pin "9") (pinfunction "P1W_9") (pintype "bidirectional"))
      (node (ref "R32") (pin "2") (pinfunction "2_2") (pintype "passive"))
    )
    (net (code "108") (name "Net-(IC13-P2W)") (class "Default")
      (node (ref "IC13") (pin "19") (pinfunction "P2W_19") (pintype "bidirectional"))
      (node (ref "R40") (pin "1") (pinfunction "1_1") (pintype "passive"))
    )
    (net (code "109") (name "Net-(IC13-P3W)") (class "Default")
      (node (ref "IC13") (pin "2") (pinfunction "P3W_2") (pintype "bidirectional"))
      (node (ref "R35") (pin "2") (pinfunction "2_2") (pintype "passive"))
    )
    (net (code "110") (name "Net-(IC14-P0W)") (class "Default")
      (node (ref "IC14") (pin "12") (pinfunction "P0W_12") (pintype "bidirectional"))
      (node (ref "R49") (pin "1") (pinfunction "1_1") (pintype "passive"))
    )
    (net (code "111") (name "Net-(IC14-P1W)") (class "Default")
      (node (ref "IC14") (pin "9") (pinfunction "P1W_9") (pintype "bidirectional"))
      (node (ref "R34") (pin "2") (pinfunction "2_2") (pintype "passive"))
    )
    (net (code "112") (name "Net-(IC14-P2W)") (class "Default")
      (node (ref "IC14") (pin "19") (pinfunction "P2W_19") (pintype "bidirectional"))
      (node (ref "R48") (pin "1") (pinfunction "1_1") (pintype "passive"))
    )
    (net (code "113") (name "Net-(IC14-P3W)") (class "Default")
      (node (ref "IC14") (pin "2") (pinfunction "P3W_2") (pintype "bidirectional"))
      (node (ref "R33") (pin "2") (pinfunction "2_2") (pintype "passive"))
    )
    (net (code "114") (name "Net-(IC15-P0W)") (class "Default")
      (node (ref "IC15") (pin "12") (pinfunction "P0W_12") (pintype "bidirectional"))
      (node (ref "R59") (pin "1") (pinfunction "1_1") (pintype "passive"))
    )
    (net (code "115") (name "Net-(IC15-P1W)") (class "Default")
      (node (ref "IC15") (pin "9") (pinfunction "P1W_9") (pintype "bidirectional"))
      (node (ref "R56") (pin "2") (pinfunction "2_2") (pintype "passive"))
    )
    (net (code "116") (name "Net-(IC15-P2W)") (class "Default")
      (node (ref "IC15") (pin "19") (pinfunction "P2W_19") (pintype "bidirectional"))
      (node (ref "R58") (pin "1") (pinfunction "1_1") (pintype "passive"))
    )
    (net (code "117") (name "Net-(IC15-P3W)") (class "Default")
      (node (ref "IC15") (pin "2") (pinfunction "P3W_2") (pintype "bidirectional"))
      (node (ref "R57") (pin "2") (pinfunction "2_2") (pintype "passive"))
    )
    (net (code "118") (name "Net-(IC16-P0W)") (class "Default")
      (node (ref "IC16") (pin "12") (pinfunction "P0W_12") (pintype "bidirectional"))
      (node (ref "R61") (pin "1") (pinfunction "1_1") (pintype "passive"))
    )
    (net (code "119") (name "Net-(IC16-P1W)") (class "Default")
      (node (ref "IC16") (pin "9") (pinfunction "P1W_9") (pintype "bidirectional"))
      (node (ref "R53") (pin "2") (pinfunction "2_2") (pintype "passive"))
    )
    (net (code "120") (name "Net-(IC16-P2W)") (class "Default")
      (node (ref "IC16") (pin "19") (pinfunction "P2W_19") (pintype "bidirectional"))
      (node (ref "R60") (pin "1") (pinfunction "1_1") (pintype "passive"))
    )
    (net (code "121") (name "Net-(IC16-P3W)") (class "Default")
      (node (ref "IC16") (pin "2") (pinfunction "P3W_2") (pintype "bidirectional"))
      (node (ref "R54") (pin "2") (pinfunction "2_2") (pintype "passive"))
    )
    (net (code "122") (name "Net-(IC17-P0W)") (class "Default")
      (node (ref "IC17") (pin "12") (pinfunction "P0W_12") (pintype "bidirectional"))
      (node (ref "R73") (pin "1") (pinfunction "1_1") (pintype "passive"))
    )
    (net (code "123") (name "Net-(IC17-P1W)") (class "Default")
      (node (ref "IC17") (pin "9") (pinfunction "P1W_9") (pintype "bidirectional"))
      (node (ref "R50") (pin "2") (pinfunction "2_2") (pintype "passive"))
    )
    (net (code "124") (name "Net-(IC17-P2W)") (class "Default")
      (node (ref "IC17") (pin "19") (pinfunction "P2W_19") (pintype "bidirectional"))
      (node (ref "R72") (pin "1") (pinfunction "1_1") (pintype "passive"))
    )
    (net (code "125") (name "Net-(IC17-P3W)") (class "Default")
      (node (ref "IC17") (pin "2") (pinfunction "P3W_2") (pintype "bidirectional"))
      (node (ref "R51") (pin "2") (pinfunction "2_2") (pintype "passive"))
    )
    (net (code "126") (name "Net-(IC18A-+IN)") (class "Default")
      (node (ref "IC18") (pin "3") (pinfunction "+IN_3") (pintype "input"))
      (node (ref "R93") (pin "2") (pinfunction "S_2") (pintype "passive"))
    )
    (net (code "127") (name "Net-(IC18B--IN)") (class "Default")
      (node (ref "IC18") (pin "6") (pinfunction "-IN_6") (pintype "input"))
      (node (ref "IC18") (pin "7") (pinfunction "OUT_7") (pintype "output"))
    )
    (net (code "128") (name "Net-(IN1-3)") (class "Default")
      (node (ref "IN1") (pin "1") (pinfunction "3_1") (pintype "passive"))
      (node (ref "R75") (pin "1") (pinfunction "1_1") (pintype "passive"))
    )
    (net (code "129") (name "Net-(IN2-3)") (class "Default")
      (node (ref "IN2") (pin "1") (pinfunction "3_1") (pintype "passive"))
      (node (ref "R76") (pin "1") (pinfunction "1_1") (pintype "passive"))
    )
    (net (code "130") (name "Net-(IN3-3)") (class "Default")
      (node (ref "IN3") (pin "1") (pinfunction "3_1") (pintype "passive"))
      (node (ref "R77") (pin "1") (pinfunction "1_1") (pintype "passive"))
    )
    (net (code "131") (name "Net-(IN4-3)") (class "Default")
      (node (ref "IN4") (pin "1") (pinfunction "3_1") (pintype "passive"))
      (node (ref "R74") (pin "1") (pinfunction "1_1") (pintype "passive"))
    )
    (net (code "132") (name "Net-(IN5-3)") (class "Default")
      (node (ref "IN5") (pin "1") (pinfunction "3_1") (pintype "passive"))
      (node (ref "R20") (pin "1") (pinfunction "1_1") (pintype "passive"))
    )
    (net (code "133") (name "Net-(IN6-3)") (class "Default")
      (node (ref "IN6") (pin "1") (pinfunction "3_1") (pintype "passive"))
      (node (ref "R46") (pin "1") (pinfunction "1_1") (pintype "passive"))
    )
    (net (code "134") (name "Net-(OUT1-3)") (class "Default")
      (node (ref "OUT1") (pin "1") (pinfunction "3_1") (pintype "passive"))
      (node (ref "R1") (pin "2") (pinfunction "2_2") (pintype "passive"))
      (node (ref "R3") (pin "2") (pinfunction "2_2") (pintype "passive"))
    )
    (net (code "135") (name "Net-(OUT2-3)") (class "Default")
      (node (ref "OUT2") (pin "1") (pinfunction "3_1") (pintype "passive"))
      (node (ref "R4") (pin "2") (pinfunction "2_2") (pintype "passive"))
      (node (ref "R6") (pin "2") (pinfunction "2_2") (pintype "passive"))
    )
    (net (code "136") (name "Net-(OUT3-3)") (class "Default")
      (node (ref "OUT3") (pin "1") (pinfunction "3_1") (pintype "passive"))
      (node (ref "R14") (pin "2") (pinfunction "2_2") (pintype "passive"))
      (node (ref "R9") (pin "2") (pinfunction "2_2") (pintype "passive"))
    )
    (net (code "137") (name "Net-(OUT4-3)") (class "Default")
      (node (ref "OUT4") (pin "1") (pinfunction "3_1") (pintype "passive"))
      (node (ref "R16") (pin "2") (pinfunction "2_2") (pintype "passive"))
      (node (ref "R18") (pin "2") (pinfunction "2_2") (pintype "passive"))
    )
    (net (code "138") (name "Net-(OUT5-3)") (class "Default")
      (node (ref "OUT5") (pin "1") (pinfunction "3_1") (pintype "passive"))
      (node (ref "R39") (pin "2") (pinfunction "2_2") (pintype "passive"))
      (node (ref "R41") (pin "2") (pinfunction "2_2") (pintype "passive"))
    )
    (net (code "139") (name "Net-(OUT6-3)") (class "Default")
      (node (ref "OUT6") (pin "1") (pinfunction "3_1") (pintype "passive"))
      (node (ref "R42") (pin "2") (pinfunction "2_2") (pintype "passive"))
      (node (ref "R44") (pin "2") (pinfunction "2_2") (pintype "passive"))
    )
    (net (code "140") (name "Net-(R93-A)") (class "Default")
      (node (ref "R93") (pin "3") (pinfunction "A_3") (pintype "passive"))
      (node (ref "R94") (pin "1") (pinfunction "1_1") (pintype "passive"))
    )
    (net (code "141") (name "Net-(R93-E)") (class "Default")
      (node (ref "R93") (pin "1") (pinfunction "E_1") (pintype "passive"))
      (node (ref "R95") (pin "2") (pinfunction "2_2") (pintype "passive"))
    )
    (net (code "142") (name "unconnected-(IC4-NC-Pad14)") (class "Default")
      (node (ref "IC4") (pin "14") (pinfunction "NC_14") (pintype "no_connect"))
    )
    (net (code "143") (name "unconnected-(IC4-~{RESET}-Pad15)") (class "Default")
      (node (ref "IC4") (pin "15") (pinfunction "~{RESET}_15") (pintype "bidirectional"))
    )
    (net (code "144") (name "unconnected-(IC6-Pad3V3-1)") (class "Default")
      (node (ref "IC6") (pin "3V3-1") (pinfunction "3V3-1_3V3-1") (pintype "bidirectional"))
    )
    (net (code "145") (name "unconnected-(IC10-NC-Pad14)") (class "Default")
      (node (ref "IC10") (pin "14") (pinfunction "NC_14") (pintype "no_connect"))
    )
    (net (code "146") (name "unconnected-(IC10-~{RESET}-Pad15)") (class "Default")
      (node (ref "IC10") (pin "15") (pinfunction "~{RESET}_15") (pintype "bidirectional"))
    )
    (net (code "147") (name "unconnected-(IC11-NC-Pad14)") (class "Default")
      (node (ref "IC11") (pin "14") (pinfunction "NC_14") (pintype "no_connect"))
    )
    (net (code "148") (name "unconnected-(IC11-~{RESET}-Pad15)") (class "Default")
      (node (ref "IC11") (pin "15") (pinfunction "~{RESET}_15") (pintype "bidirectional"))
    )
    (net (code "149") (name "unconnected-(IC12-NC-Pad14)") (class "Default")
      (node (ref "IC12") (pin "14") (pinfunction "NC_14") (pintype "no_connect"))
    )
    (net (code "150") (name "unconnected-(IC12-~{RESET}-Pad15)") (class "Default")
      (node (ref "IC12") (pin "15") (pinfunction "~{RESET}_15") (pintype "bidirectional"))
    )
    (net (code "151") (name "unconnected-(IC13-NC-Pad14)") (class "Default")
      (node (ref "IC13") (pin "14") (pinfunction "NC_14") (pintype "no_connect"))
    )
    (net (code "152") (name "unconnected-(IC13-~{RESET}-Pad15)") (class "Default")
      (node (ref "IC13") (pin "15") (pinfunction "~{RESET}_15") (pintype "bidirectional"))
    )
    (net (code "153") (name "unconnected-(IC14-NC-Pad14)") (class "Default")
      (node (ref "IC14") (pin "14") (pinfunction "NC_14") (pintype "no_connect"))
    )
    (net (code "154") (name "unconnected-(IC14-~{RESET}-Pad15)") (class "Default")
      (node (ref "IC14") (pin "15") (pinfunction "~{RESET}_15") (pintype "bidirectional"))
    )
    (net (code "155") (name "unconnected-(IC15-NC-Pad14)") (class "Default")
      (node (ref "IC15") (pin "14") (pinfunction "NC_14") (pintype "no_connect"))
    )
    (net (code "156") (name "unconnected-(IC15-~{RESET}-Pad15)") (class "Default")
      (node (ref "IC15") (pin "15") (pinfunction "~{RESET}_15") (pintype "bidirectional"))
    )
    (net (code "157") (name "unconnected-(IC16-NC-Pad14)") (class "Default")
      (node (ref "IC16") (pin "14") (pinfunction "NC_14") (pintype "no_connect"))
    )
    (net (code "158") (name "unconnected-(IC16-~{RESET}-Pad15)") (class "Default")
      (node (ref "IC16") (pin "15") (pinfunction "~{RESET}_15") (pintype "bidirectional"))
    )
    (net (code "159") (name "unconnected-(IC17-NC-Pad14)") (class "Default")
      (node (ref "IC17") (pin "14") (pinfunction "NC_14") (pintype "no_connect"))
    )
    (net (code "160") (name "unconnected-(IC17-~{RESET}-Pad15)") (class "Default")
      (node (ref "IC17") (pin "15") (pinfunction "~{RESET}_15") (pintype "bidirectional"))
    )
  )
)
